# MOD-EEG-SMT.net
KiCad netlist of a schematic drawn in EAGLE
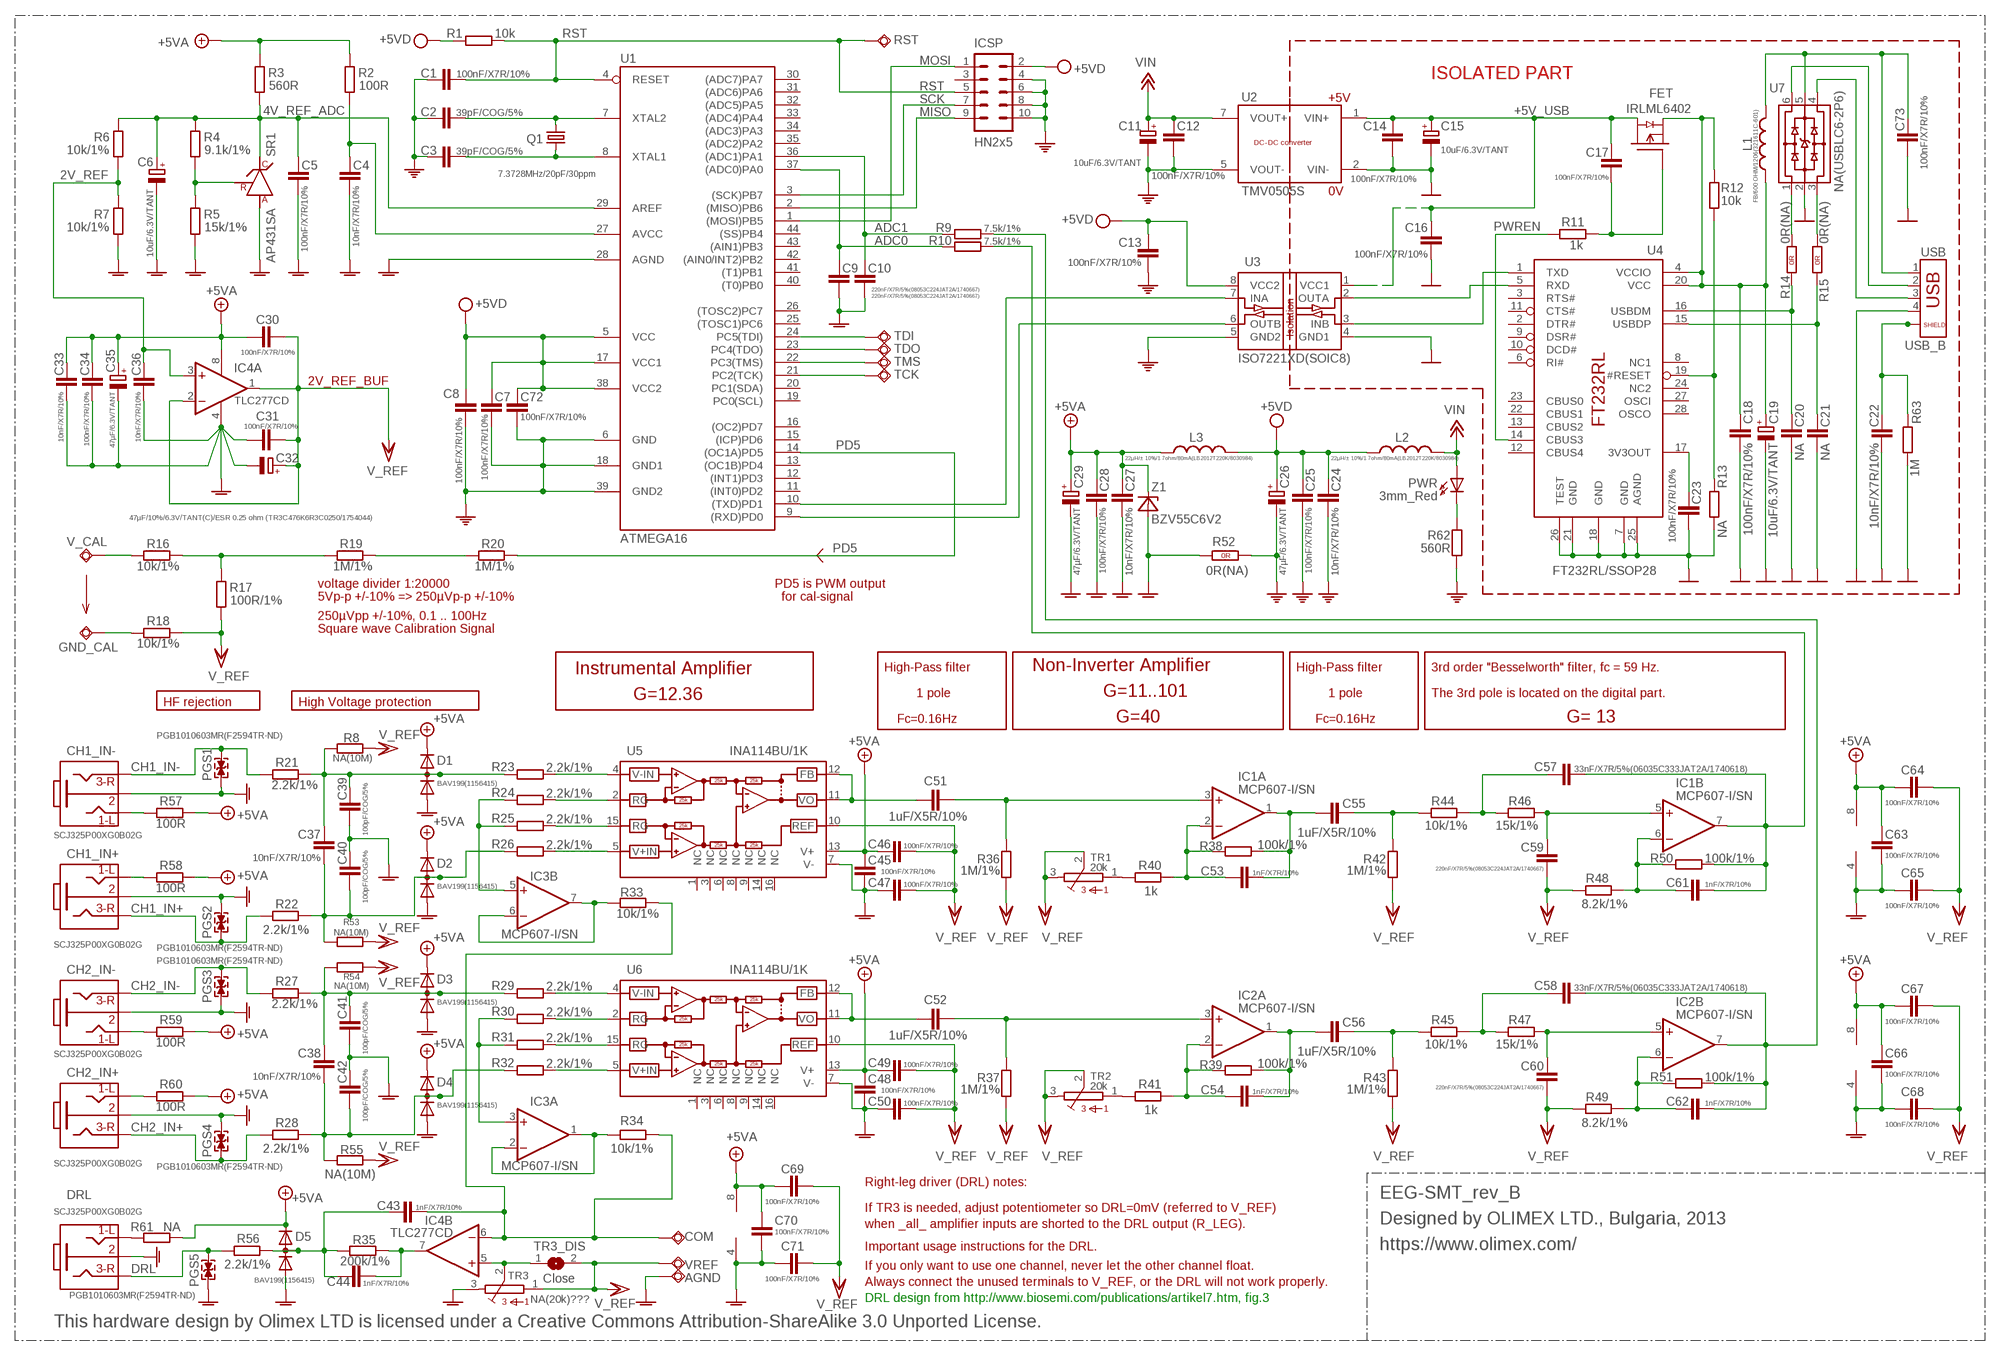
[diagram p0: schematic, sheet 1]

(export (version "E")
  (design (tool "Eeschema 10.0.6"))
  (components
    (comp (ref "AGND")
      (value "TESTPAD3")
      (footprint "eagle-import:TEST_PAD40_70_SQUARE")
      (libsource (lib "eagle-import") (part "TESTPAD3"))
    )
    (comp (ref "C1")
      (value "100nF/X7R/10%")
      (footprint "eagle-import:C0603_DWS")
      (libsource (lib "eagle-import") (part "C-EUC0603_DWS"))
    )
    (comp (ref "C2")
      (value "39pF/COG/5%")
      (footprint "eagle-import:C0603_DWS")
      (libsource (lib "eagle-import") (part "C-EUC0603_DWS"))
    )
    (comp (ref "C3")
      (value "39pF/COG/5%")
      (footprint "eagle-import:C0603_DWS")
      (libsource (lib "eagle-import") (part "C-EUC0603_DWS"))
    )
    (comp (ref "C4")
      (value "10nF/X7R/10%")
      (footprint "eagle-import:C0603_DWS")
      (libsource (lib "eagle-import") (part "C-EUC0603_DWS"))
    )
    (comp (ref "C5")
      (value "100nF/X7R/10%")
      (footprint "eagle-import:C0603_DWS")
      (libsource (lib "eagle-import") (part "C-EUC0603_DWS"))
    )
    (comp (ref "C6")
      (value "10uF/6.3V/TANT")
      (footprint "eagle-import:CT3216")
      (libsource (lib "eagle-import") (part "CPOL-EUCT3216"))
    )
    (comp (ref "C7")
      (value "100nF/X7R/10%")
      (footprint "eagle-import:C0603_DWS")
      (libsource (lib "eagle-import") (part "C-EUC0603_DWS"))
    )
    (comp (ref "C8")
      (value "100nF/X7R/10%")
      (footprint "eagle-import:C0603_DWS")
      (libsource (lib "eagle-import") (part "C-EUC0603_DWS"))
    )
    (comp (ref "C9")
      (value "220nF/X7R/5%(08053C224JAT2A/1740667)")
      (footprint "eagle-import:C0805_5MIL_DWS")
      (libsource (lib "eagle-import") (part "C-EUC0805_5MIL_DWS"))
    )
    (comp (ref "C10")
      (value "220nF/X7R/5%(08053C224JAT2A/1740667)")
      (footprint "eagle-import:C0805_5MIL_DWS")
      (libsource (lib "eagle-import") (part "C-EUC0805_5MIL_DWS"))
    )
    (comp (ref "C11")
      (value "10uF/6.3V/TANT")
      (footprint "eagle-import:CT3216")
      (libsource (lib "eagle-import") (part "CPOL-EUCT3216"))
    )
    (comp (ref "C12")
      (value "100nF/X7R/10%")
      (footprint "eagle-import:C0603_DWS")
      (libsource (lib "eagle-import") (part "C-EUC0603_DWS"))
    )
    (comp (ref "C13")
      (value "100nF/X7R/10%")
      (footprint "eagle-import:C0603_DWS")
      (libsource (lib "eagle-import") (part "C-EUC0603_DWS"))
    )
    (comp (ref "C14")
      (value "100nF/X7R/10%")
      (footprint "eagle-import:C0603_DWS")
      (libsource (lib "eagle-import") (part "C-EUC0603_DWS"))
    )
    (comp (ref "C15")
      (value "10uF/6.3V/TANT")
      (footprint "eagle-import:CT3216")
      (libsource (lib "eagle-import") (part "CPOL-EUCT3216"))
    )
    (comp (ref "C16")
      (value "100nF/X7R/10%")
      (footprint "eagle-import:C0603_DWS")
      (libsource (lib "eagle-import") (part "C-EUC0603_DWS"))
    )
    (comp (ref "C17")
      (value "100nF/X7R/10%")
      (footprint "eagle-import:C0603_DWS")
      (libsource (lib "eagle-import") (part "C-EUC0603_DWS"))
    )
    (comp (ref "C18")
      (value "100nF/X7R/10%")
      (footprint "eagle-import:C0603_DWS")
      (libsource (lib "eagle-import") (part "C-EUC0603_DWS"))
    )
    (comp (ref "C19")
      (value "10uF/6.3V/TANT")
      (footprint "eagle-import:CT3216")
      (libsource (lib "eagle-import") (part "CPOL-EUCT3216"))
    )
    (comp (ref "C20")
      (value "NA")
      (footprint "eagle-import:C0603_DWS_NA")
      (libsource (lib "eagle-import") (part "C-EUC0603_DWS_NA"))
    )
    (comp (ref "C21")
      (value "NA")
      (footprint "eagle-import:C0603_DWS_NA")
      (libsource (lib "eagle-import") (part "C-EUC0603_DWS_NA"))
    )
    (comp (ref "C22")
      (value "10nF/X7R/10%")
      (footprint "eagle-import:C0603_DWS")
      (libsource (lib "eagle-import") (part "C-EUC0603_DWS"))
    )
    (comp (ref "C23")
      (value "100nF/X7R/10%")
      (footprint "eagle-import:C0603_DWS")
      (libsource (lib "eagle-import") (part "C-EUC0603_DWS"))
    )
    (comp (ref "C24")
      (value "10nF/X7R/10%")
      (footprint "eagle-import:C0603_DWS")
      (libsource (lib "eagle-import") (part "C-EUC0603_DWS"))
    )
    (comp (ref "C25")
      (value "100nF/X7R/10%")
      (footprint "eagle-import:C0603_DWS")
      (libsource (lib "eagle-import") (part "C-EUC0603_DWS"))
    )
    (comp (ref "C26")
      (value "47µF/6.3V/TANT")
      (footprint "eagle-import:CT3528")
      (libsource (lib "eagle-import") (part "CPOL-EUCT3528"))
    )
    (comp (ref "C27")
      (value "10nF/X7R/10%")
      (footprint "eagle-import:C0603_DWS")
      (libsource (lib "eagle-import") (part "C-EUC0603_DWS"))
    )
    (comp (ref "C28")
      (value "100nF/X7R/10%")
      (footprint "eagle-import:C0603_DWS")
      (libsource (lib "eagle-import") (part "C-EUC0603_DWS"))
    )
    (comp (ref "C29")
      (value "47µF/6.3V/TANT")
      (footprint "eagle-import:CT3528")
      (libsource (lib "eagle-import") (part "CPOL-EUCT3528"))
    )
    (comp (ref "C30")
      (value "100nF/X7R/10%")
      (footprint "eagle-import:C0603_DWS")
      (libsource (lib "eagle-import") (part "C-EUC0603_DWS"))
    )
    (comp (ref "C31")
      (value "100nF/X7R/10%")
      (footprint "eagle-import:C0603_DWS")
      (libsource (lib "eagle-import") (part "C-EUC0603_DWS"))
    )
    (comp (ref "C32")
      (value "47µF/10%/6.3V/TANT(C)/ESR 0.25 ohm (TR3C476K6R3C0250/1754044)")
      (footprint "eagle-import:CT6032")
      (libsource (lib "eagle-import") (part "CPOL-EUCT6032"))
    )
    (comp (ref "C33")
      (value "10nF/X7R/10%")
      (footprint "eagle-import:C0603_DWS")
      (libsource (lib "eagle-import") (part "C-EUC0603_DWS"))
    )
    (comp (ref "C34")
      (value "100nF/X7R/10%")
      (footprint "eagle-import:C0603_DWS")
      (libsource (lib "eagle-import") (part "C-EUC0603_DWS"))
    )
    (comp (ref "C35")
      (value "47µF/6.3V/TANT")
      (footprint "eagle-import:CT3528")
      (libsource (lib "eagle-import") (part "CPOL-EUCT3528"))
    )
    (comp (ref "C36")
      (value "10nF/X7R/10%")
      (footprint "eagle-import:C0603_DWS")
      (libsource (lib "eagle-import") (part "C-EUC0603_DWS"))
    )
    (comp (ref "C37")
      (value "10nF/X7R/10%")
      (footprint "eagle-import:C0603_DWS")
      (libsource (lib "eagle-import") (part "C-EUC0603_DWS"))
    )
    (comp (ref "C38")
      (value "10nF/X7R/10%")
      (footprint "eagle-import:C0603_DWS")
      (libsource (lib "eagle-import") (part "C-EUC0603_DWS"))
    )
    (comp (ref "C39")
      (value "100pF/COG/5%")
      (footprint "eagle-import:C0603_DWS")
      (libsource (lib "eagle-import") (part "C-EUC0603_DWS"))
    )
    (comp (ref "C40")
      (value "100pF/COG/5%")
      (footprint "eagle-import:C0603_DWS")
      (libsource (lib "eagle-import") (part "C-EUC0603_DWS"))
    )
    (comp (ref "C41")
      (value "100pF/COG/5%")
      (footprint "eagle-import:C0603_DWS")
      (libsource (lib "eagle-import") (part "C-EUC0603_DWS"))
    )
    (comp (ref "C42")
      (value "100pF/COG/5%")
      (footprint "eagle-import:C0603_DWS")
      (libsource (lib "eagle-import") (part "C-EUC0603_DWS"))
    )
    (comp (ref "C43")
      (value "1nF/X7R/10%")
      (footprint "eagle-import:C0603_DWS")
      (libsource (lib "eagle-import") (part "C-EUC0603_DWS"))
    )
    (comp (ref "C44")
      (value "1nF/X7R/10%")
      (footprint "eagle-import:C0603_DWS")
      (libsource (lib "eagle-import") (part "C-EUC0603_DWS"))
    )
    (comp (ref "C45")
      (value "100nF/X7R/10%")
      (footprint "eagle-import:C0603_DWS")
      (libsource (lib "eagle-import") (part "C-EUC0603_DWS"))
    )
    (comp (ref "C46")
      (value "100nF/X7R/10%")
      (footprint "eagle-import:C0603_DWS")
      (libsource (lib "eagle-import") (part "C-EUC0603_DWS"))
    )
    (comp (ref "C47")
      (value "100nF/X7R/10%")
      (footprint "eagle-import:C0603_DWS")
      (libsource (lib "eagle-import") (part "C-EUC0603_DWS"))
    )
    (comp (ref "C48")
      (value "100nF/X7R/10%")
      (footprint "eagle-import:C0603_DWS")
      (libsource (lib "eagle-import") (part "C-EUC0603_DWS"))
    )
    (comp (ref "C49")
      (value "100nF/X7R/10%")
      (footprint "eagle-import:C0603_DWS")
      (libsource (lib "eagle-import") (part "C-EUC0603_DWS"))
    )
    (comp (ref "C50")
      (value "100nF/X7R/10%")
      (footprint "eagle-import:C0603_DWS")
      (libsource (lib "eagle-import") (part "C-EUC0603_DWS"))
    )
    (comp (ref "C51")
      (value "1uF/X5R/10%")
      (footprint "eagle-import:C0603_DWS")
      (libsource (lib "eagle-import") (part "C-EUC0603_DWS"))
    )
    (comp (ref "C52")
      (value "1uF/X5R/10%")
      (footprint "eagle-import:C0603_DWS")
      (libsource (lib "eagle-import") (part "C-EUC0603_DWS"))
    )
    (comp (ref "C53")
      (value "1nF/X7R/10%")
      (footprint "eagle-import:C0603_DWS")
      (libsource (lib "eagle-import") (part "C-EUC0603_DWS"))
    )
    (comp (ref "C54")
      (value "1nF/X7R/10%")
      (footprint "eagle-import:C0603_DWS")
      (libsource (lib "eagle-import") (part "C-EUC0603_DWS"))
    )
    (comp (ref "C55")
      (value "1uF/X5R/10%")
      (footprint "eagle-import:C0603_DWS")
      (libsource (lib "eagle-import") (part "C-EUC0603_DWS"))
    )
    (comp (ref "C56")
      (value "1uF/X5R/10%")
      (footprint "eagle-import:C0603_DWS")
      (libsource (lib "eagle-import") (part "C-EUC0603_DWS"))
    )
    (comp (ref "C57")
      (value "33nF/X7R/5%(06035C333JAT2A/1740618)")
      (footprint "eagle-import:C0603_DWS")
      (libsource (lib "eagle-import") (part "C-EUC0603_DWS"))
    )
    (comp (ref "C58")
      (value "33nF/X7R/5%(06035C333JAT2A/1740618)")
      (footprint "eagle-import:C0603_DWS")
      (libsource (lib "eagle-import") (part "C-EUC0603_DWS"))
    )
    (comp (ref "C59")
      (value "220nF/X7R/5%(08053C224JAT2A/1740667)")
      (footprint "eagle-import:C0805_5MIL_DWS")
      (libsource (lib "eagle-import") (part "C-EUC0805_5MIL_DWS"))
    )
    (comp (ref "C60")
      (value "220nF/X7R/5%(08053C224JAT2A/1740667)")
      (footprint "eagle-import:C0805_5MIL_DWS")
      (libsource (lib "eagle-import") (part "C-EUC0805_5MIL_DWS"))
    )
    (comp (ref "C61")
      (value "1nF/X7R/10%")
      (footprint "eagle-import:C0603_DWS")
      (libsource (lib "eagle-import") (part "C-EUC0603_DWS"))
    )
    (comp (ref "C62")
      (value "1nF/X7R/10%")
      (footprint "eagle-import:C0603_DWS")
      (libsource (lib "eagle-import") (part "C-EUC0603_DWS"))
    )
    (comp (ref "C63")
      (value "100nF/X7R/10%")
      (footprint "eagle-import:C0603_DWS")
      (libsource (lib "eagle-import") (part "C-EUC0603_DWS"))
    )
    (comp (ref "C64")
      (value "100nF/X7R/10%")
      (footprint "eagle-import:C0603_DWS")
      (libsource (lib "eagle-import") (part "C-EUC0603_DWS"))
    )
    (comp (ref "C65")
      (value "100nF/X7R/10%")
      (footprint "eagle-import:C0603_DWS")
      (libsource (lib "eagle-import") (part "C-EUC0603_DWS"))
    )
    (comp (ref "C66")
      (value "100nF/X7R/10%")
      (footprint "eagle-import:C0603_DWS")
      (libsource (lib "eagle-import") (part "C-EUC0603_DWS"))
    )
    (comp (ref "C67")
      (value "100nF/X7R/10%")
      (footprint "eagle-import:C0603_DWS")
      (libsource (lib "eagle-import") (part "C-EUC0603_DWS"))
    )
    (comp (ref "C68")
      (value "100nF/X7R/10%")
      (footprint "eagle-import:C0603_DWS")
      (libsource (lib "eagle-import") (part "C-EUC0603_DWS"))
    )
    (comp (ref "C69")
      (value "100nF/X7R/10%")
      (footprint "eagle-import:C0603_DWS")
      (libsource (lib "eagle-import") (part "C-EUC0603_DWS"))
    )
    (comp (ref "C70")
      (value "100nF/X7R/10%")
      (footprint "eagle-import:C0603_DWS")
      (libsource (lib "eagle-import") (part "C-EUC0603_DWS"))
    )
    (comp (ref "C71")
      (value "100nF/X7R/10%")
      (footprint "eagle-import:C0603_DWS")
      (libsource (lib "eagle-import") (part "C-EUC0603_DWS"))
    )
    (comp (ref "C72")
      (value "100nF/X7R/10%")
      (footprint "eagle-import:C0603_DWS")
      (libsource (lib "eagle-import") (part "C-EUC0603_DWS"))
    )
    (comp (ref "C73")
      (value "100nF/X7R/10%")
      (footprint "eagle-import:C0603_DWS")
      (libsource (lib "eagle-import") (part "C-EUC0603_DWS"))
    )
    (comp (ref "CH1_IN+")
      (value "SCJ325P00XG0B02G")
      (footprint "eagle-import:PHONE_JACK-SMD")
      (libsource (lib "eagle-import") (part "JACK-3PINPHONE_JACK-SMD"))
    )
    (comp (ref "CH1_IN-")
      (value "SCJ325P00XG0B02G")
      (footprint "eagle-import:PHONE_JACK-SMD")
      (libsource (lib "eagle-import") (part "JACK-3PINPHONE_JACK-SMD"))
    )
    (comp (ref "CH2_IN+")
      (value "SCJ325P00XG0B02G")
      (footprint "eagle-import:PHONE_JACK-SMD")
      (libsource (lib "eagle-import") (part "JACK-3PINPHONE_JACK-SMD"))
    )
    (comp (ref "CH2_IN-")
      (value "SCJ325P00XG0B02G")
      (footprint "eagle-import:PHONE_JACK-SMD")
      (libsource (lib "eagle-import") (part "JACK-3PINPHONE_JACK-SMD"))
    )
    (comp (ref "COM")
      (value "TESTPAD3")
      (footprint "eagle-import:TEST_PAD40_70_SQUARE")
      (libsource (lib "eagle-import") (part "TESTPAD3"))
    )
    (comp (ref "D1")
      (value "BAV199(1156415)")
      (footprint "eagle-import:SOT23C(BAT54S)")
      (libsource (lib "eagle-import") (part "DIODE_AC-AC_"))
    )
    (comp (ref "D2")
      (value "BAV199(1156415)")
      (footprint "eagle-import:SOT23C(BAT54S)")
      (libsource (lib "eagle-import") (part "DIODE_AC-AC_"))
    )
    (comp (ref "D3")
      (value "BAV199(1156415)")
      (footprint "eagle-import:SOT23C(BAT54S)")
      (libsource (lib "eagle-import") (part "DIODE_AC-AC_"))
    )
    (comp (ref "D4")
      (value "BAV199(1156415)")
      (footprint "eagle-import:SOT23C(BAT54S)")
      (libsource (lib "eagle-import") (part "DIODE_AC-AC_"))
    )
    (comp (ref "D5")
      (value "BAV199(1156415)")
      (footprint "eagle-import:SOT23C(BAT54S)")
      (libsource (lib "eagle-import") (part "DIODE_AC-AC_"))
    )
    (comp (ref "DRL")
      (value "SCJ325P00XG0B02G")
      (footprint "eagle-import:PHONE_JACK-SMD")
      (libsource (lib "eagle-import") (part "JACK-3PINPHONE_JACK-SMD"))
    )
    (comp (ref "FET")
      (value "IRLML6402")
      (footprint "eagle-import:SOT23")
      (libsource (lib "eagle-import") (part "IRLML6402"))
    )
    (comp (ref "GND_CAL")
      (value "TESTPAD3")
      (footprint "eagle-import:TEST_PAD40_70_SQUARE")
      (libsource (lib "eagle-import") (part "TESTPAD3"))
    )
    (comp (ref "IC1")
      (value "MCP607-I/SN")
      (footprint "eagle-import:SO08")
      (libsource (lib "eagle-import") (part "LM358D"))
    )
    (comp (ref "IC2")
      (value "MCP607-I/SN")
      (footprint "eagle-import:SO08")
      (libsource (lib "eagle-import") (part "LM358D"))
    )
    (comp (ref "IC3")
      (value "MCP607-I/SN")
      (footprint "eagle-import:SO08")
      (libsource (lib "eagle-import") (part "LM358D"))
    )
    (comp (ref "IC4")
      (value "TLC277CD")
      (footprint "eagle-import:SO08")
      (libsource (lib "eagle-import") (part "LM358D"))
    )
    (comp (ref "ICSP")
      (value "HN2x5")
      (footprint "eagle-import:ML10_NEW")
      (libsource (lib "eagle-import") (part "ML10ML10_NEW"))
    )
    (comp (ref "L1")
      (value "FB/600 OHM/1206(321611C-601)")
      (footprint "eagle-import:L1206_5MIL")
      (libsource (lib "eagle-import") (part "L-US1206_5MIL"))
    )
    (comp (ref "L2")
      (value "22µH/± 10%/1.7ohm/80mA(LB2012T220K/8030984)")
      (footprint "eagle-import:L0805_5MIL_DWS")
      (libsource (lib "eagle-import") (part "L-USL0805_5MIL_DWS"))
    )
    (comp (ref "L3")
      (value "22µH/± 10%/1.7ohm/80mA(LB2012T220K/8030984)")
      (footprint "eagle-import:L0805_5MIL_DWS")
      (libsource (lib "eagle-import") (part "L-USL0805_5MIL_DWS"))
    )
    (comp (ref "PGS1")
      (value "PGB1010603MR(F2594TR-ND)")
      (footprint "eagle-import:0603")
      (libsource (lib "eagle-import") (part "PGB1010603MR(F2594TR-ND)"))
    )
    (comp (ref "PGS2")
      (value "PGB1010603MR(F2594TR-ND)")
      (footprint "eagle-import:0603")
      (libsource (lib "eagle-import") (part "PGB1010603MR(F2594TR-ND)"))
    )
    (comp (ref "PGS3")
      (value "PGB1010603MR(F2594TR-ND)")
      (footprint "eagle-import:0603")
      (libsource (lib "eagle-import") (part "PGB1010603MR(F2594TR-ND)"))
    )
    (comp (ref "PGS4")
      (value "PGB1010603MR(F2594TR-ND)")
      (footprint "eagle-import:0603")
      (libsource (lib "eagle-import") (part "PGB1010603MR(F2594TR-ND)"))
    )
    (comp (ref "PGS5")
      (value "PGB1010603MR(F2594TR-ND)")
      (footprint "eagle-import:0603")
      (libsource (lib "eagle-import") (part "PGB1010603MR(F2594TR-ND)"))
    )
    (comp (ref "PWR")
      (value "3mm_Red")
      (footprint "eagle-import:LED-3.0MM")
      (libsource (lib "eagle-import") (part "LED3.0MM"))
    )
    (comp (ref "Q1")
      (value "7.3728MHz/20pF/30ppm")
      (footprint "eagle-import:HC49_SMD2_THIN")
      (libsource (lib "eagle-import") (part "HC49/S1"))
    )
    (comp (ref "R1")
      (value "10k")
      (footprint "eagle-import:R0603_5MIL_DWS")
      (libsource (lib "eagle-import") (part "R-EU_R0603_5MIL_DWS"))
    )
    (comp (ref "R2")
      (value "100R")
      (footprint "eagle-import:R0603_5MIL_DWS")
      (libsource (lib "eagle-import") (part "R-EU_R0603_5MIL_DWS"))
    )
    (comp (ref "R3")
      (value "560R")
      (footprint "eagle-import:R0603_5MIL_DWS")
      (libsource (lib "eagle-import") (part "R-EU_R0603_5MIL_DWS"))
    )
    (comp (ref "R4")
      (value "9.1k/1%")
      (footprint "eagle-import:R0603_5MIL_DWS")
      (libsource (lib "eagle-import") (part "R-EU_R0603_5MIL_DWS"))
    )
    (comp (ref "R5")
      (value "15k/1%")
      (footprint "eagle-import:R0603_5MIL_DWS")
      (libsource (lib "eagle-import") (part "R-EU_R0603_5MIL_DWS"))
    )
    (comp (ref "R6")
      (value "10k/1%")
      (footprint "eagle-import:R0603_5MIL_DWS")
      (libsource (lib "eagle-import") (part "R-EU_R0603_5MIL_DWS"))
    )
    (comp (ref "R7")
      (value "10k/1%")
      (footprint "eagle-import:R0603_5MIL_DWS")
      (libsource (lib "eagle-import") (part "R-EU_R0603_5MIL_DWS"))
    )
    (comp (ref "R8")
      (value "NA(10M)")
      (footprint "eagle-import:R0603_5MIL_DWS")
      (libsource (lib "eagle-import") (part "R-EU_R0603_5MIL_DWS"))
    )
    (comp (ref "R9")
      (value "7.5k/1%")
      (footprint "eagle-import:R0603_5MIL_DWS")
      (libsource (lib "eagle-import") (part "R-EU_R0603_5MIL_DWS"))
    )
    (comp (ref "R10")
      (value "7.5k/1%")
      (footprint "eagle-import:R0603_5MIL_DWS")
      (libsource (lib "eagle-import") (part "R-EU_R0603_5MIL_DWS"))
    )
    (comp (ref "R11")
      (value "1k")
      (footprint "eagle-import:R0603_5MIL_DWS")
      (libsource (lib "eagle-import") (part "R-EU_R0603_5MIL_DWS"))
    )
    (comp (ref "R12")
      (value "10k")
      (footprint "eagle-import:R0603_5MIL_DWS")
      (libsource (lib "eagle-import") (part "R-EU_R0603_5MIL_DWS"))
    )
    (comp (ref "R13")
      (value "NA")
      (footprint "eagle-import:R0603_5MIL_DWS_NA")
      (libsource (lib "eagle-import") (part "R-EU_R0603_5MIL_DWS_NA"))
    )
    (comp (ref "R14")
      (value "0R(NA)")
      (footprint "eagle-import:0603_0R")
      (libsource (lib "eagle-import") (part "R_0R0R(NA)"))
    )
    (comp (ref "R15")
      (value "0R(NA)")
      (footprint "eagle-import:0603_0R")
      (libsource (lib "eagle-import") (part "R_0R0R(NA)"))
    )
    (comp (ref "R16")
      (value "10k/1%")
      (footprint "eagle-import:R0603_5MIL_DWS")
      (libsource (lib "eagle-import") (part "R-EU_R0603_5MIL_DWS"))
    )
    (comp (ref "R17")
      (value "100R/1%")
      (footprint "eagle-import:R0603_5MIL_DWS")
      (libsource (lib "eagle-import") (part "R-EU_R0603_5MIL_DWS"))
    )
    (comp (ref "R18")
      (value "10k/1%")
      (footprint "eagle-import:R0603_5MIL_DWS")
      (libsource (lib "eagle-import") (part "R-EU_R0603_5MIL_DWS"))
    )
    (comp (ref "R19")
      (value "1M/1%")
      (footprint "eagle-import:R0603_5MIL_DWS")
      (libsource (lib "eagle-import") (part "R-EU_R0603_5MIL_DWS"))
    )
    (comp (ref "R20")
      (value "1M/1%")
      (footprint "eagle-import:R0603_5MIL_DWS")
      (libsource (lib "eagle-import") (part "R-EU_R0603_5MIL_DWS"))
    )
    (comp (ref "R21")
      (value "2.2k/1%")
      (footprint "eagle-import:R0603_5MIL_DWS")
      (libsource (lib "eagle-import") (part "R-EU_R0603_5MIL_DWS"))
    )
    (comp (ref "R22")
      (value "2.2k/1%")
      (footprint "eagle-import:R0603_5MIL_DWS")
      (libsource (lib "eagle-import") (part "R-EU_R0603_5MIL_DWS"))
    )
    (comp (ref "R23")
      (value "2.2k/1%")
      (footprint "eagle-import:R0603_5MIL_DWS")
      (libsource (lib "eagle-import") (part "R-EU_R0603_5MIL_DWS"))
    )
    (comp (ref "R24")
      (value "2.2k/1%")
      (footprint "eagle-import:R0603_5MIL_DWS")
      (libsource (lib "eagle-import") (part "R-EU_R0603_5MIL_DWS"))
    )
    (comp (ref "R25")
      (value "2.2k/1%")
      (footprint "eagle-import:R0603_5MIL_DWS")
      (libsource (lib "eagle-import") (part "R-EU_R0603_5MIL_DWS"))
    )
    (comp (ref "R26")
      (value "2.2k/1%")
      (footprint "eagle-import:R0603_5MIL_DWS")
      (libsource (lib "eagle-import") (part "R-EU_R0603_5MIL_DWS"))
    )
    (comp (ref "R27")
      (value "2.2k/1%")
      (footprint "eagle-import:R0603_5MIL_DWS")
      (libsource (lib "eagle-import") (part "R-EU_R0603_5MIL_DWS"))
    )
    (comp (ref "R28")
      (value "2.2k/1%")
      (footprint "eagle-import:R0603_5MIL_DWS")
      (libsource (lib "eagle-import") (part "R-EU_R0603_5MIL_DWS"))
    )
    (comp (ref "R29")
      (value "2.2k/1%")
      (footprint "eagle-import:R0603_5MIL_DWS")
      (libsource (lib "eagle-import") (part "R-EU_R0603_5MIL_DWS"))
    )
    (comp (ref "R30")
      (value "2.2k/1%")
      (footprint "eagle-import:R0603_5MIL_DWS")
      (libsource (lib "eagle-import") (part "R-EU_R0603_5MIL_DWS"))
    )
    (comp (ref "R31")
      (value "2.2k/1%")
      (footprint "eagle-import:R0603_5MIL_DWS")
      (libsource (lib "eagle-import") (part "R-EU_R0603_5MIL_DWS"))
    )
    (comp (ref "R32")
      (value "2.2k/1%")
      (footprint "eagle-import:R0603_5MIL_DWS")
      (libsource (lib "eagle-import") (part "R-EU_R0603_5MIL_DWS"))
    )
    (comp (ref "R33")
      (value "10k/1%")
      (footprint "eagle-import:R0603_5MIL_DWS")
      (libsource (lib "eagle-import") (part "R-EU_R0603_5MIL_DWS"))
    )
    (comp (ref "R34")
      (value "10k/1%")
      (footprint "eagle-import:R0603_5MIL_DWS")
      (libsource (lib "eagle-import") (part "R-EU_R0603_5MIL_DWS"))
    )
    (comp (ref "R35")
      (value "200k/1%")
      (footprint "eagle-import:R0603_5MIL_DWS")
      (libsource (lib "eagle-import") (part "R-EU_R0603_5MIL_DWS"))
    )
    (comp (ref "R36")
      (value "1M/1%")
      (footprint "eagle-import:R0603_5MIL_DWS")
      (libsource (lib "eagle-import") (part "R-EU_R0603_5MIL_DWS"))
    )
    (comp (ref "R37")
      (value "1M/1%")
      (footprint "eagle-import:R0603_5MIL_DWS")
      (libsource (lib "eagle-import") (part "R-EU_R0603_5MIL_DWS"))
    )
    (comp (ref "R38")
      (value "100k/1%")
      (footprint "eagle-import:R0603_5MIL_DWS")
      (libsource (lib "eagle-import") (part "R-EU_R0603_5MIL_DWS"))
    )
    (comp (ref "R39")
      (value "100k/1%")
      (footprint "eagle-import:R0603_5MIL_DWS")
      (libsource (lib "eagle-import") (part "R-EU_R0603_5MIL_DWS"))
    )
    (comp (ref "R40")
      (value "1k")
      (footprint "eagle-import:R0603_5MIL_DWS")
      (libsource (lib "eagle-import") (part "R-EU_R0603_5MIL_DWS"))
    )
    (comp (ref "R41")
      (value "1k")
      (footprint "eagle-import:R0603_5MIL_DWS")
      (libsource (lib "eagle-import") (part "R-EU_R0603_5MIL_DWS"))
    )
    (comp (ref "R42")
      (value "1M/1%")
      (footprint "eagle-import:R0603_5MIL_DWS")
      (libsource (lib "eagle-import") (part "R-EU_R0603_5MIL_DWS"))
    )
    (comp (ref "R43")
      (value "1M/1%")
      (footprint "eagle-import:R0603_5MIL_DWS")
      (libsource (lib "eagle-import") (part "R-EU_R0603_5MIL_DWS"))
    )
    (comp (ref "R44")
      (value "10k/1%")
      (footprint "eagle-import:R0603_5MIL_DWS")
      (libsource (lib "eagle-import") (part "R-EU_R0603_5MIL_DWS"))
    )
    (comp (ref "R45")
      (value "10k/1%")
      (footprint "eagle-import:R0603_5MIL_DWS")
      (libsource (lib "eagle-import") (part "R-EU_R0603_5MIL_DWS"))
    )
    (comp (ref "R46")
      (value "15k/1%")
      (footprint "eagle-import:R0603_5MIL_DWS")
      (libsource (lib "eagle-import") (part "R-EU_R0603_5MIL_DWS"))
    )
    (comp (ref "R47")
      (value "15k/1%")
      (footprint "eagle-import:R0603_5MIL_DWS")
      (libsource (lib "eagle-import") (part "R-EU_R0603_5MIL_DWS"))
    )
    (comp (ref "R48")
      (value "8.2k/1%")
      (footprint "eagle-import:R0603_5MIL_DWS")
      (libsource (lib "eagle-import") (part "R-EU_R0603_5MIL_DWS"))
    )
    (comp (ref "R49")
      (value "8.2k/1%")
      (footprint "eagle-import:R0603_5MIL_DWS")
      (libsource (lib "eagle-import") (part "R-EU_R0603_5MIL_DWS"))
    )
    (comp (ref "R50")
      (value "100k/1%")
      (footprint "eagle-import:R0603_5MIL_DWS")
      (libsource (lib "eagle-import") (part "R-EU_R0603_5MIL_DWS"))
    )
    (comp (ref "R51")
      (value "100k/1%")
      (footprint "eagle-import:R0603_5MIL_DWS")
      (libsource (lib "eagle-import") (part "R-EU_R0603_5MIL_DWS"))
    )
    (comp (ref "R52")
      (value "0R(NA)")
      (footprint "eagle-import:0603_0R")
      (libsource (lib "eagle-import") (part "R_0R0R(NA)"))
    )
    (comp (ref "R53")
      (value "NA(10M)")
      (footprint "eagle-import:R0603_5MIL_DWS")
      (libsource (lib "eagle-import") (part "R-EU_R0603_5MIL_DWS"))
    )
    (comp (ref "R54")
      (value "NA(10M)")
      (footprint "eagle-import:R0603_5MIL_DWS")
      (libsource (lib "eagle-import") (part "R-EU_R0603_5MIL_DWS"))
    )
    (comp (ref "R55")
      (value "NA(10M)")
      (footprint "eagle-import:R0603_5MIL_DWS")
      (libsource (lib "eagle-import") (part "R-EU_R0603_5MIL_DWS"))
    )
    (comp (ref "R56")
      (value "2.2k/1%")
      (footprint "eagle-import:R0603_5MIL_DWS")
      (libsource (lib "eagle-import") (part "R-EU_R0603_5MIL_DWS"))
    )
    (comp (ref "R57")
      (value "100R")
      (footprint "eagle-import:R0603_5MIL_DWS")
      (libsource (lib "eagle-import") (part "R-EU_R0603_5MIL_DWS"))
    )
    (comp (ref "R58")
      (value "100R")
      (footprint "eagle-import:R0603_5MIL_DWS")
      (libsource (lib "eagle-import") (part "R-EU_R0603_5MIL_DWS"))
    )
    (comp (ref "R59")
      (value "100R")
      (footprint "eagle-import:R0603_5MIL_DWS")
      (libsource (lib "eagle-import") (part "R-EU_R0603_5MIL_DWS"))
    )
    (comp (ref "R60")
      (value "100R")
      (footprint "eagle-import:R0603_5MIL_DWS")
      (libsource (lib "eagle-import") (part "R-EU_R0603_5MIL_DWS"))
    )
    (comp (ref "R61")
      (value "NA")
      (footprint "eagle-import:R0603_5MIL_DWS_NA")
      (libsource (lib "eagle-import") (part "R-EU_R0603_5MIL_DWS_NA"))
    )
    (comp (ref "R62")
      (value "560R")
      (footprint "eagle-import:R0603_5MIL_DWS")
      (libsource (lib "eagle-import") (part "R-EU_R0603_5MIL_DWS"))
    )
    (comp (ref "R63")
      (value "1M")
      (footprint "eagle-import:R0603_5MIL_DWS")
      (libsource (lib "eagle-import") (part "R-EU_R0603_5MIL_DWS"))
    )
    (comp (ref "RST")
      (value "TESTPAD80/30")
      (footprint "eagle-import:SMD80_30")
      (libsource (lib "eagle-import") (part "TESTPAD80/30"))
    )
    (comp (ref "SR1")
      (value "AP431SA")
      (footprint "eagle-import:SOT-23")
      (libsource (lib "eagle-import") (part "TL431'''"))
    )
    (comp (ref "TCK")
      (value "TESTPAD80/30")
      (footprint "eagle-import:SMD80_30")
      (libsource (lib "eagle-import") (part "TESTPAD80/30"))
    )
    (comp (ref "TDI")
      (value "TESTPAD80/30")
      (footprint "eagle-import:SMD80_30")
      (libsource (lib "eagle-import") (part "TESTPAD80/30"))
    )
    (comp (ref "TDO")
      (value "TESTPAD80/30")
      (footprint "eagle-import:SMD80_30")
      (libsource (lib "eagle-import") (part "TESTPAD80/30"))
    )
    (comp (ref "TMS")
      (value "TESTPAD80/30")
      (footprint "eagle-import:SMD80_30")
      (libsource (lib "eagle-import") (part "TESTPAD80/30"))
    )
    (comp (ref "TR1")
      (value "20k")
      (footprint "eagle-import:S64Y")
      (libsource (lib "eagle-import") (part "S64Y"))
    )
    (comp (ref "TR2")
      (value "20k")
      (footprint "eagle-import:S64Y")
      (libsource (lib "eagle-import") (part "S64Y"))
    )
    (comp (ref "TR3")
      (value "NA(20k)???")
      (footprint "eagle-import:S64Y")
      (libsource (lib "eagle-import") (part "S64Y"))
    )
    (comp (ref "TR3_DIS")
      (value "Close")
      (footprint "eagle-import:SJ_1_SMALLER")
      (libsource (lib "eagle-import") (part "SJSJ_SMALLER"))
    )
    (comp (ref "U1")
      (value "ATMEGA16")
      (footprint "eagle-import:44TQFP")
      (libsource (lib "eagle-import") (part "ATMEGA16"))
    )
    (comp (ref "U2")
      (value "TMV0505S")
      (footprint "eagle-import:TMADCDC")
      (libsource (lib "eagle-import") (part "TMV0505"))
    )
    (comp (ref "U3")
      (value "ISO7221XD(SOIC8)")
      (footprint "eagle-import:SO-8_ISOLATE")
      (libsource (lib "eagle-import") (part "ISO7221XD"))
    )
    (comp (ref "U4")
      (value "FT232RL/SSOP28")
      (footprint "eagle-import:SSOP28")
      (libsource (lib "eagle-import") (part "FT232RLSSOP28"))
    )
    (comp (ref "U5")
      (value "INA114BU/1K")
      (footprint "eagle-import:SO16")
      (libsource (lib "eagle-import") (part "INA114BU/1K"))
    )
    (comp (ref "U6")
      (value "INA114BU/1K")
      (footprint "eagle-import:SO16")
      (libsource (lib "eagle-import") (part "INA114BU/1K"))
    )
    (comp (ref "U7")
      (value "NA(USBLC6-2P6)")
      (footprint "eagle-import:USBLC6-2P6")
      (libsource (lib "eagle-import") (part "USBLC6-2"))
    )
    (comp (ref "USB")
      (value "USB_B")
      (footprint "eagle-import:USB_NEAR_BLACK")
      (libsource (lib "eagle-import") (part "USB_SHIELD"))
    )
    (comp (ref "VREF")
      (value "TESTPAD3")
      (footprint "eagle-import:TEST_PAD40_70_SQUARE")
      (libsource (lib "eagle-import") (part "TESTPAD3"))
    )
    (comp (ref "V_CAL")
      (value "TESTPAD3")
      (footprint "eagle-import:TEST_PAD40_70_SQUARE")
      (libsource (lib "eagle-import") (part "TESTPAD3"))
    )
    (comp (ref "Z1")
      (value "BZV55C6V2")
      (footprint "eagle-import:MINI-MELF")
      (libsource (lib "eagle-import") (part "ZDIOD-SMD"))
    )
  )
  (nets
    (net (code "1") (name "+5VA") (class "Default")
      (node (ref "C27") (pin "1") (pinfunction "1_1") (pintype "passive"))
      (node (ref "C28") (pin "1") (pinfunction "1_1") (pintype "passive"))
      (node (ref "C29") (pin "+") (pinfunction "+_+") (pintype "passive"))
      (node (ref "C30") (pin "2") (pinfunction "2_2") (pintype "passive"))
      (node (ref "C33") (pin "1") (pinfunction "1_1") (pintype "passive"))
      (node (ref "C34") (pin "1") (pinfunction "1_1") (pintype "passive"))
      (node (ref "C35") (pin "+") (pinfunction "+_+") (pintype "passive"))
      (node (ref "C45") (pin "1") (pinfunction "1_1") (pintype "passive"))
      (node (ref "C46") (pin "1") (pinfunction "1_1") (pintype "passive"))
      (node (ref "C48") (pin "1") (pinfunction "1_1") (pintype "passive"))
      (node (ref "C49") (pin "1") (pinfunction "1_1") (pintype "passive"))
      (node (ref "C63") (pin "1") (pinfunction "1_1") (pintype "passive"))
      (node (ref "C64") (pin "1") (pinfunction "1_1") (pintype "passive"))
      (node (ref "C66") (pin "1") (pinfunction "1_1") (pintype "passive"))
      (node (ref "C67") (pin "1") (pinfunction "1_1") (pintype "passive"))
      (node (ref "C69") (pin "1") (pinfunction "1_1") (pintype "passive"))
      (node (ref "C70") (pin "1") (pinfunction "1_1") (pintype "passive"))
      (node (ref "D1") (pin "2") (pinfunction "K_2") (pintype "passive"))
      (node (ref "D2") (pin "2") (pinfunction "K_2") (pintype "passive"))
      (node (ref "D3") (pin "2") (pinfunction "K_2") (pintype "passive"))
      (node (ref "D4") (pin "2") (pinfunction "K_2") (pintype "passive"))
      (node (ref "D5") (pin "2") (pinfunction "K_2") (pintype "passive"))
      (node (ref "IC1") (pin "8") (pinfunction "V+_8") (pintype "power_in"))
      (node (ref "IC2") (pin "8") (pinfunction "V+_8") (pintype "power_in"))
      (node (ref "IC3") (pin "8") (pinfunction "V+_8") (pintype "power_in"))
      (node (ref "IC4") (pin "8") (pinfunction "V+_8") (pintype "power_in"))
      (node (ref "L3") (pin "2") (pinfunction "2_2") (pintype "passive"))
      (node (ref "R2") (pin "2") (pinfunction "2_2") (pintype "passive"))
      (node (ref "R3") (pin "2") (pinfunction "2_2") (pintype "passive"))
      (node (ref "R57") (pin "2") (pinfunction "2_2") (pintype "passive"))
      (node (ref "R58") (pin "2") (pinfunction "2_2") (pintype "passive"))
      (node (ref "R59") (pin "2") (pinfunction "2_2") (pintype "passive"))
      (node (ref "R60") (pin "2") (pinfunction "2_2") (pintype "passive"))
      (node (ref "R61") (pin "2") (pinfunction "2_2") (pintype "passive"))
      (node (ref "U5") (pin "13") (pinfunction "V+_13") (pintype "power_in"))
      (node (ref "U6") (pin "13") (pinfunction "V+_13") (pintype "power_in"))
      (node (ref "Z1") (pin "1") (pinfunction "C_1") (pintype "passive"))
    )
    (net (code "2") (name "+5VD") (class "Default")
      (node (ref "C13") (pin "1") (pinfunction "1_1") (pintype "passive"))
      (node (ref "C24") (pin "1") (pinfunction "1_1") (pintype "passive"))
      (node (ref "C25") (pin "1") (pinfunction "1_1") (pintype "passive"))
      (node (ref "C26") (pin "+") (pinfunction "+_+") (pintype "passive"))
      (node (ref "C7") (pin "1") (pinfunction "1_1") (pintype "passive"))
      (node (ref "C72") (pin "1") (pinfunction "1_1") (pintype "passive"))
      (node (ref "C8") (pin "1") (pinfunction "1_1") (pintype "passive"))
      (node (ref "ICSP") (pin "2") (pinfunction "2_2") (pintype "passive"))
      (node (ref "L2") (pin "2") (pinfunction "2_2") (pintype "passive"))
      (node (ref "L3") (pin "1") (pinfunction "1_1") (pintype "passive"))
      (node (ref "R1") (pin "1") (pinfunction "1_1") (pintype "passive"))
      (node (ref "U1") (pin "17") (pinfunction "VCC1_17") (pintype "bidirectional"))
      (node (ref "U1") (pin "38") (pinfunction "VCC2_38") (pintype "bidirectional"))
      (node (ref "U1") (pin "5") (pinfunction "VCC_5") (pintype "power_in"))
      (node (ref "U3") (pin "8") (pinfunction "VCC2_8") (pintype "power_in"))
    )
    (net (code "3") (name "/+5V_USB") (class "Default")
      (node (ref "C14") (pin "1") (pinfunction "1_1") (pintype "passive"))
      (node (ref "C15") (pin "+") (pinfunction "+_+") (pintype "passive"))
      (node (ref "C16") (pin "1") (pinfunction "1_1") (pintype "passive"))
      (node (ref "C17") (pin "1") (pinfunction "1_1") (pintype "passive"))
      (node (ref "FET") (pin "3") (pinfunction "D_3") (pintype "passive"))
      (node (ref "U2") (pin "1") (pinfunction "VIN+_1") (pintype "power_in"))
      (node (ref "U3") (pin "1") (pinfunction "VCC1_1") (pintype "power_in"))
    )
    (net (code "4") (name "/2V_REF") (class "Default")
      (node (ref "C36") (pin "1") (pinfunction "1_1") (pintype "passive"))
      (node (ref "IC4") (pin "3") (pinfunction "+IN_3") (pintype "input"))
      (node (ref "R6") (pin "1") (pinfunction "1_1") (pintype "passive"))
      (node (ref "R7") (pin "2") (pinfunction "2_2") (pintype "passive"))
    )
    (net (code "5") (name "/4V_REF_ADC") (class "Default")
      (node (ref "C5") (pin "1") (pinfunction "1_1") (pintype "passive"))
      (node (ref "C6") (pin "+") (pinfunction "+_+") (pintype "passive"))
      (node (ref "R3") (pin "1") (pinfunction "1_1") (pintype "passive"))
      (node (ref "R4") (pin "2") (pinfunction "2_2") (pintype "passive"))
      (node (ref "R6") (pin "2") (pinfunction "2_2") (pintype "passive"))
      (node (ref "SR1") (pin "1") (pinfunction "C_1") (pintype "input"))
      (node (ref "U1") (pin "29") (pinfunction "AREF_29") (pintype "power_in"))
    )
    (net (code "6") (name "/ADC0") (class "Default")
      (node (ref "C9") (pin "1") (pinfunction "1_1") (pintype "passive"))
      (node (ref "R10") (pin "1") (pinfunction "1_1") (pintype "passive"))
      (node (ref "U1") (pin "37") (pinfunction "(ADC0)PA0_37") (pintype "bidirectional"))
    )
    (net (code "7") (name "/ADC1") (class "Default")
      (node (ref "C10") (pin "1") (pinfunction "1_1") (pintype "passive"))
      (node (ref "R9") (pin "1") (pinfunction "1_1") (pintype "passive"))
      (node (ref "U1") (pin "36") (pinfunction "(ADC1)PA1_36") (pintype "bidirectional"))
    )
    (net (code "8") (name "/CH1_IN+") (class "Default")
      (node (ref "CH1_IN+") (pin "2") (pinfunction "3_2") (pintype "bidirectional"))
      (node (ref "PGS2") (pin "1") (pinfunction "1_1") (pintype "input"))
      (node (ref "R22") (pin "1") (pinfunction "1_1") (pintype "passive"))
    )
    (net (code "9") (name "/CH1_IN-") (class "Default")
      (node (ref "CH1_IN-") (pin "2") (pinfunction "3_2") (pintype "bidirectional"))
      (node (ref "PGS1") (pin "2") (pinfunction "2_2") (pintype "input"))
      (node (ref "R21") (pin "1") (pinfunction "1_1") (pintype "passive"))
    )
    (net (code "10") (name "/CH2_IN+") (class "Default")
      (node (ref "CH2_IN+") (pin "2") (pinfunction "3_2") (pintype "bidirectional"))
      (node (ref "PGS4") (pin "1") (pinfunction "1_1") (pintype "input"))
      (node (ref "R28") (pin "1") (pinfunction "1_1") (pintype "passive"))
    )
    (net (code "11") (name "/CH2_IN-") (class "Default")
      (node (ref "CH2_IN-") (pin "2") (pinfunction "3_2") (pintype "bidirectional"))
      (node (ref "PGS3") (pin "2") (pinfunction "2_2") (pintype "input"))
      (node (ref "R27") (pin "1") (pinfunction "1_1") (pintype "passive"))
    )
    (net (code "12") (name "/DRL") (class "Default")
      (node (ref "DRL") (pin "2") (pinfunction "3_2") (pintype "bidirectional"))
      (node (ref "PGS5") (pin "2") (pinfunction "2_2") (pintype "input"))
      (node (ref "R56") (pin "1") (pinfunction "1_1") (pintype "passive"))
    )
    (net (code "13") (name "/MISO") (class "Default")
      (node (ref "ICSP") (pin "9") (pinfunction "9_9") (pintype "passive"))
      (node (ref "U1") (pin "2") (pinfunction "(MISO)PB6_2") (pintype "bidirectional"))
    )
    (net (code "14") (name "/MOSI") (class "Default")
      (node (ref "ICSP") (pin "1") (pinfunction "1_1") (pintype "passive"))
      (node (ref "U1") (pin "1") (pinfunction "(MOSI)PB5_1") (pintype "bidirectional"))
    )
    (net (code "15") (name "/PD5") (class "Default")
      (node (ref "R20") (pin "2") (pinfunction "2_2") (pintype "passive"))
      (node (ref "U1") (pin "14") (pinfunction "(OC1A)PD5_14") (pintype "bidirectional"))
    )
    (net (code "16") (name "/PWREN") (class "Default")
      (node (ref "R11") (pin "1") (pinfunction "1_1") (pintype "passive"))
      (node (ref "U4") (pin "14") (pinfunction "CBUS3_14") (pintype "bidirectional"))
    )
    (net (code "17") (name "/RST") (class "Default")
      (node (ref "C1") (pin "1") (pinfunction "1_1") (pintype "passive"))
      (node (ref "ICSP") (pin "5") (pinfunction "5_5") (pintype "passive"))
      (node (ref "R1") (pin "2") (pinfunction "2_2") (pintype "passive"))
      (node (ref "RST") (pin "P$1") (pinfunction "PP_P$1") (pintype "passive"))
      (node (ref "U1") (pin "4") (pinfunction "RESET_4") (pintype "input"))
    )
    (net (code "18") (name "/SCK") (class "Default")
      (node (ref "ICSP") (pin "7") (pinfunction "7_7") (pintype "passive"))
      (node (ref "U1") (pin "3") (pinfunction "(SCK)PB7_3") (pintype "bidirectional"))
    )
    (net (code "19") (name "GND") (class "Default")
      (node (ref "C14") (pin "2") (pinfunction "2_2") (pintype "passive"))
      (node (ref "C15") (pin "-") (pinfunction "-_-") (pintype "passive"))
      (node (ref "C16") (pin "2") (pinfunction "2_2") (pintype "passive"))
      (node (ref "C18") (pin "2") (pinfunction "2_2") (pintype "passive"))
      (node (ref "C19") (pin "-") (pinfunction "-_-") (pintype "passive"))
      (node (ref "C20") (pin "2") (pinfunction "2_2") (pintype "passive"))
      (node (ref "C21") (pin "2") (pinfunction "2_2") (pintype "passive"))
      (node (ref "C22") (pin "2") (pinfunction "2_2") (pintype "passive"))
      (node (ref "C23") (pin "2") (pinfunction "2_2") (pintype "passive"))
      (node (ref "C73") (pin "2") (pinfunction "2_2") (pintype "passive"))
      (node (ref "R13") (pin "1") (pinfunction "1_1") (pintype "passive"))
      (node (ref "R63") (pin "1") (pinfunction "1_1") (pintype "passive"))
      (node (ref "U2") (pin "2") (pinfunction "VIN-_2") (pintype "power_in"))
      (node (ref "U3") (pin "4") (pinfunction "GND1_4") (pintype "power_in"))
      (node (ref "U4") (pin "18") (pinfunction "GND_18") (pintype "power_in"))
      (node (ref "U4") (pin "21") (pinfunction "GND_21") (pintype "power_in"))
      (node (ref "U4") (pin "25") (pinfunction "AGND_25") (pintype "power_in"))
      (node (ref "U4") (pin "26") (pinfunction "TEST_26") (pintype "bidirectional"))
      (node (ref "U4") (pin "7") (pinfunction "GND_7") (pintype "power_in"))
      (node (ref "U7") (pin "2") (pinfunction "2_2") (pintype "power_in"))
      (node (ref "USB") (pin "4") (pinfunction "4_4") (pintype "passive"))
    )
    (net (code "20") (name "GNDA") (class "Default")
      (node (ref "AGND") (pin "P$1") (pinfunction "PP_P$1") (pintype "passive"))
      (node (ref "C10") (pin "2") (pinfunction "2_2") (pintype "passive"))
      (node (ref "C27") (pin "2") (pinfunction "2_2") (pintype "passive"))
      (node (ref "C28") (pin "2") (pinfunction "2_2") (pintype "passive"))
      (node (ref "C29") (pin "-") (pinfunction "-_-") (pintype "passive"))
      (node (ref "C31") (pin "2") (pinfunction "2_2") (pintype "passive"))
      (node (ref "C32") (pin "-") (pinfunction "-_-") (pintype "passive"))
      (node (ref "C33") (pin "2") (pinfunction "2_2") (pintype "passive"))
      (node (ref "C34") (pin "2") (pinfunction "2_2") (pintype "passive"))
      (node (ref "C35") (pin "-") (pinfunction "-_-") (pintype "passive"))
      (node (ref "C36") (pin "2") (pinfunction "2_2") (pintype "passive"))
      (node (ref "C39") (pin "1") (pinfunction "1_1") (pintype "passive"))
      (node (ref "C4") (pin "2") (pinfunction "2_2") (pintype "passive"))
      (node (ref "C40") (pin "2") (pinfunction "2_2") (pintype "passive"))
      (node (ref "C41") (pin "1") (pinfunction "1_1") (pintype "passive"))
      (node (ref "C42") (pin "2") (pinfunction "2_2") (pintype "passive"))
      (node (ref "C45") (pin "2") (pinfunction "2_2") (pintype "passive"))
      (node (ref "C47") (pin "1") (pinfunction "1_1") (pintype "passive"))
      (node (ref "C48") (pin "2") (pinfunction "2_2") (pintype "passive"))
      (node (ref "C5") (pin "2") (pinfunction "2_2") (pintype "passive"))
      (node (ref "C50") (pin "1") (pinfunction "1_1") (pintype "passive"))
      (node (ref "C6") (pin "-") (pinfunction "-_-") (pintype "passive"))
      (node (ref "C63") (pin "2") (pinfunction "2_2") (pintype "passive"))
      (node (ref "C65") (pin "1") (pinfunction "1_1") (pintype "passive"))
      (node (ref "C66") (pin "2") (pinfunction "2_2") (pintype "passive"))
      (node (ref "C68") (pin "1") (pinfunction "1_1") (pintype "passive"))
      (node (ref "C70") (pin "2") (pinfunction "2_2") (pintype "passive"))
      (node (ref "C71") (pin "1") (pinfunction "1_1") (pintype "passive"))
      (node (ref "C9") (pin "2") (pinfunction "2_2") (pintype "passive"))
      (node (ref "CH1_IN+") (pin "1") (pinfunction "2_1") (pintype "input"))
      (node (ref "CH1_IN-") (pin "1") (pinfunction "2_1") (pintype "input"))
      (node (ref "CH2_IN+") (pin "1") (pinfunction "2_1") (pintype "input"))
      (node (ref "CH2_IN-") (pin "1") (pinfunction "2_1") (pintype "input"))
      (node (ref "D1") (pin "1") (pinfunction "A_1") (pintype "passive"))
      (node (ref "D2") (pin "1") (pinfunction "A_1") (pintype "passive"))
      (node (ref "D3") (pin "1") (pinfunction "A_1") (pintype "passive"))
      (node (ref "D4") (pin "1") (pinfunction "A_1") (pintype "passive"))
      (node (ref "D5") (pin "1") (pinfunction "A_1") (pintype "passive"))
      (node (ref "DRL") (pin "1") (pinfunction "2_1") (pintype "input"))
      (node (ref "IC1") (pin "4") (pinfunction "V-_4") (pintype "power_in"))
      (node (ref "IC2") (pin "4") (pinfunction "V-_4") (pintype "power_in"))
      (node (ref "IC3") (pin "4") (pinfunction "V-_4") (pintype "power_in"))
      (node (ref "IC4") (pin "4") (pinfunction "V-_4") (pintype "power_in"))
      (node (ref "PGS1") (pin "1") (pinfunction "1_1") (pintype "input"))
      (node (ref "PGS2") (pin "2") (pinfunction "2_2") (pintype "input"))
      (node (ref "PGS3") (pin "1") (pinfunction "1_1") (pintype "input"))
      (node (ref "PGS4") (pin "2") (pinfunction "2_2") (pintype "input"))
      (node (ref "PGS5") (pin "1") (pinfunction "1_1") (pintype "input"))
      (node (ref "R5") (pin "1") (pinfunction "1_1") (pintype "passive"))
      (node (ref "R52") (pin "1") (pinfunction "1.1_1") (pintype "passive"))
      (node (ref "R7") (pin "1") (pinfunction "1_1") (pintype "passive"))
      (node (ref "SR1") (pin "3") (pinfunction "A_3") (pintype "input"))
      (node (ref "TR3") (pin "3") (pinfunction "3_3") (pintype "passive"))
      (node (ref "U1") (pin "28") (pinfunction "AGND_28") (pintype "power_in"))
      (node (ref "U5") (pin "7") (pinfunction "V-_7") (pintype "power_in"))
      (node (ref "U6") (pin "7") (pinfunction "V-_7") (pintype "power_in"))
      (node (ref "Z1") (pin "2") (pinfunction "A_2") (pintype "passive"))
    )
    (net (code "21") (name "Net-(C55-Pad2)") (class "Default")
      (node (ref "C55") (pin "2") (pinfunction "2_2") (pintype "passive"))
      (node (ref "R42") (pin "1") (pinfunction "1_1") (pintype "passive"))
      (node (ref "R44") (pin "1") (pinfunction "1_1") (pintype "passive"))
    )
    (net (code "22") (name "Net-(C56-Pad2)") (class "Default")
      (node (ref "C56") (pin "2") (pinfunction "2_2") (pintype "passive"))
      (node (ref "R43") (pin "1") (pinfunction "1_1") (pintype "passive"))
      (node (ref "R45") (pin "1") (pinfunction "1_1") (pintype "passive"))
    )
    (net (code "23") (name "Net-(C57-Pad1)") (class "Default")
      (node (ref "C57") (pin "1") (pinfunction "1_1") (pintype "passive"))
      (node (ref "R44") (pin "2") (pinfunction "2_2") (pintype "passive"))
      (node (ref "R46") (pin "1") (pinfunction "1_1") (pintype "passive"))
    )
    (net (code "24") (name "Net-(C58-Pad1)") (class "Default")
      (node (ref "C58") (pin "1") (pinfunction "1_1") (pintype "passive"))
      (node (ref "R45") (pin "2") (pinfunction "2_2") (pintype "passive"))
      (node (ref "R47") (pin "1") (pinfunction "1_1") (pintype "passive"))
    )
    (net (code "25") (name "Net-(C73-Pad1)") (class "Default")
      (node (ref "C73") (pin "1") (pinfunction "1_1") (pintype "passive"))
      (node (ref "L1") (pin "1") (pinfunction "1_1") (pintype "passive"))
      (node (ref "U7") (pin "5") (pinfunction "5_5") (pintype "power_in"))
      (node (ref "USB") (pin "1") (pinfunction "1_1") (pintype "passive"))
    )
    (net (code "26") (name "Net-(CH1_IN+-1)") (class "Default")
      (node (ref "CH1_IN+") (pin "5") (pinfunction "1_5") (pintype "bidirectional"))
      (node (ref "R58") (pin "1") (pinfunction "1_1") (pintype "passive"))
    )
    (net (code "27") (name "Net-(CH1_IN--1)") (class "Default")
      (node (ref "CH1_IN-") (pin "5") (pinfunction "1_5") (pintype "bidirectional"))
      (node (ref "R57") (pin "1") (pinfunction "1_1") (pintype "passive"))
    )
    (net (code "28") (name "Net-(CH2_IN+-1)") (class "Default")
      (node (ref "CH2_IN+") (pin "5") (pinfunction "1_5") (pintype "bidirectional"))
      (node (ref "R60") (pin "1") (pinfunction "1_1") (pintype "passive"))
    )
    (net (code "29") (name "Net-(CH2_IN--1)") (class "Default")
      (node (ref "CH2_IN-") (pin "5") (pinfunction "1_5") (pintype "bidirectional"))
      (node (ref "R59") (pin "1") (pinfunction "1_1") (pintype "passive"))
    )
    (net (code "30") (name "Net-(COM-PP)") (class "Default")
      (node (ref "C43") (pin "1") (pinfunction "1_1") (pintype "passive"))
      (node (ref "COM") (pin "P$1") (pinfunction "PP_P$1") (pintype "passive"))
      (node (ref "IC4") (pin "6") (pinfunction "-IN_6") (pintype "input"))
      (node (ref "R33") (pin "1") (pinfunction "1_1") (pintype "passive"))
      (node (ref "R34") (pin "1") (pinfunction "1_1") (pintype "passive"))
    )
    (net (code "31") (name "Net-(D1-AK)") (class "Default")
      (node (ref "C37") (pin "2") (pinfunction "2_2") (pintype "passive"))
      (node (ref "C39") (pin "2") (pinfunction "2_2") (pintype "passive"))
      (node (ref "D1") (pin "3") (pinfunction "AK_3") (pintype "passive"))
      (node (ref "R21") (pin "2") (pinfunction "2_2") (pintype "passive"))
      (node (ref "R23") (pin "2") (pinfunction "2_2") (pintype "passive"))
      (node (ref "R8") (pin "2") (pinfunction "2_2") (pintype "passive"))
    )
    (net (code "32") (name "Net-(D2-AK)") (class "Default")
      (node (ref "C37") (pin "1") (pinfunction "1_1") (pintype "passive"))
      (node (ref "C40") (pin "1") (pinfunction "1_1") (pintype "passive"))
      (node (ref "D2") (pin "3") (pinfunction "AK_3") (pintype "passive"))
      (node (ref "R22") (pin "2") (pinfunction "2_2") (pintype "passive"))
      (node (ref "R26") (pin "2") (pinfunction "2_2") (pintype "passive"))
      (node (ref "R53") (pin "2") (pinfunction "2_2") (pintype "passive"))
    )
    (net (code "33") (name "Net-(D3-AK)") (class "Default")
      (node (ref "C38") (pin "2") (pinfunction "2_2") (pintype "passive"))
      (node (ref "C41") (pin "2") (pinfunction "2_2") (pintype "passive"))
      (node (ref "D3") (pin "3") (pinfunction "AK_3") (pintype "passive"))
      (node (ref "R27") (pin "2") (pinfunction "2_2") (pintype "passive"))
      (node (ref "R29") (pin "2") (pinfunction "2_2") (pintype "passive"))
      (node (ref "R54") (pin "2") (pinfunction "2_2") (pintype "passive"))
    )
    (net (code "34") (name "Net-(D4-AK)") (class "Default")
      (node (ref "C38") (pin "1") (pinfunction "1_1") (pintype "passive"))
      (node (ref "C42") (pin "1") (pinfunction "1_1") (pintype "passive"))
      (node (ref "D4") (pin "3") (pinfunction "AK_3") (pintype "passive"))
      (node (ref "R28") (pin "2") (pinfunction "2_2") (pintype "passive"))
      (node (ref "R32") (pin "2") (pinfunction "2_2") (pintype "passive"))
      (node (ref "R55") (pin "2") (pinfunction "2_2") (pintype "passive"))
    )
    (net (code "35") (name "Net-(D5-AK)") (class "Default")
      (node (ref "C43") (pin "2") (pinfunction "2_2") (pintype "passive"))
      (node (ref "C44") (pin "2") (pinfunction "2_2") (pintype "passive"))
      (node (ref "D5") (pin "3") (pinfunction "AK_3") (pintype "passive"))
      (node (ref "R35") (pin "1") (pinfunction "1_1") (pintype "passive"))
      (node (ref "R56") (pin "2") (pinfunction "2_2") (pintype "passive"))
    )
    (net (code "36") (name "Net-(DRL-1)") (class "Default")
      (node (ref "DRL") (pin "5") (pinfunction "1_5") (pintype "bidirectional"))
      (node (ref "R61") (pin "1") (pinfunction "1_1") (pintype "passive"))
    )
    (net (code "37") (name "Net-(FET-G)") (class "Default")
      (node (ref "C17") (pin "2") (pinfunction "2_2") (pintype "passive"))
      (node (ref "FET") (pin "1") (pinfunction "G_1") (pintype "passive"))
      (node (ref "R11") (pin "2") (pinfunction "2_2") (pintype "passive"))
    )
    (net (code "38") (name "Net-(FET-S)") (class "Default")
      (node (ref "C18") (pin "1") (pinfunction "1_1") (pintype "passive"))
      (node (ref "C19") (pin "+") (pinfunction "+_+") (pintype "passive"))
      (node (ref "FET") (pin "2") (pinfunction "S_2") (pintype "passive"))
      (node (ref "L1") (pin "2") (pinfunction "2_2") (pintype "passive"))
      (node (ref "R12") (pin "2") (pinfunction "2_2") (pintype "passive"))
      (node (ref "U4") (pin "20") (pinfunction "VCC_20") (pintype "power_in"))
      (node (ref "U4") (pin "4") (pinfunction "VCCIO_4") (pintype "power_in"))
    )
    (net (code "39") (name "Net-(GND_CAL-PP)") (class "Default")
      (node (ref "GND_CAL") (pin "P$1") (pinfunction "PP_P$1") (pintype "passive"))
      (node (ref "R18") (pin "1") (pinfunction "1_1") (pintype "passive"))
    )
    (net (code "40") (name "Net-(IC1A-+IN)") (class "Default")
      (node (ref "C51") (pin "2") (pinfunction "2_2") (pintype "passive"))
      (node (ref "IC1") (pin "3") (pinfunction "+IN_3") (pintype "input"))
      (node (ref "R36") (pin "1") (pinfunction "1_1") (pintype "passive"))
    )
    (net (code "41") (name "Net-(IC1A--IN)") (class "Default")
      (node (ref "C53") (pin "1") (pinfunction "1_1") (pintype "passive"))
      (node (ref "IC1") (pin "2") (pinfunction "-IN_2") (pintype "input"))
      (node (ref "R38") (pin "1") (pinfunction "1_1") (pintype "passive"))
      (node (ref "R40") (pin "1") (pinfunction "1_1") (pintype "passive"))
    )
    (net (code "42") (name "Net-(IC1A-OUT)") (class "Default")
      (node (ref "C53") (pin "2") (pinfunction "2_2") (pintype "passive"))
      (node (ref "C55") (pin "1") (pinfunction "1_1") (pintype "passive"))
      (node (ref "IC1") (pin "1") (pinfunction "OUT_1") (pintype "output"))
      (node (ref "R38") (pin "2") (pinfunction "2_2") (pintype "passive"))
    )
    (net (code "43") (name "Net-(IC1B-+IN)") (class "Default")
      (node (ref "C59") (pin "1") (pinfunction "1_1") (pintype "passive"))
      (node (ref "IC1") (pin "5") (pinfunction "+IN_5") (pintype "input"))
      (node (ref "R46") (pin "2") (pinfunction "2_2") (pintype "passive"))
    )
    (net (code "44") (name "Net-(IC1B--IN)") (class "Default")
      (node (ref "C61") (pin "1") (pinfunction "1_1") (pintype "passive"))
      (node (ref "IC1") (pin "6") (pinfunction "-IN_6") (pintype "input"))
      (node (ref "R48") (pin "1") (pinfunction "1_1") (pintype "passive"))
      (node (ref "R50") (pin "1") (pinfunction "1_1") (pintype "passive"))
    )
    (net (code "45") (name "Net-(IC1B-OUT)") (class "Default")
      (node (ref "C57") (pin "2") (pinfunction "2_2") (pintype "passive"))
      (node (ref "C61") (pin "2") (pinfunction "2_2") (pintype "passive"))
      (node (ref "IC1") (pin "7") (pinfunction "OUT_7") (pintype "output"))
      (node (ref "R10") (pin "2") (pinfunction "2_2") (pintype "passive"))
      (node (ref "R50") (pin "2") (pinfunction "2_2") (pintype "passive"))
    )
    (net (code "46") (name "Net-(IC2A-+IN)") (class "Default")
      (node (ref "C52") (pin "2") (pinfunction "2_2") (pintype "passive"))
      (node (ref "IC2") (pin "3") (pinfunction "+IN_3") (pintype "input"))
      (node (ref "R37") (pin "1") (pinfunction "1_1") (pintype "passive"))
    )
    (net (code "47") (name "Net-(IC2A--IN)") (class "Default")
      (node (ref "C54") (pin "1") (pinfunction "1_1") (pintype "passive"))
      (node (ref "IC2") (pin "2") (pinfunction "-IN_2") (pintype "input"))
      (node (ref "R39") (pin "1") (pinfunction "1_1") (pintype "passive"))
      (node (ref "R41") (pin "1") (pinfunction "1_1") (pintype "passive"))
    )
    (net (code "48") (name "Net-(IC2A-OUT)") (class "Default")
      (node (ref "C54") (pin "2") (pinfunction "2_2") (pintype "passive"))
      (node (ref "C56") (pin "1") (pinfunction "1_1") (pintype "passive"))
      (node (ref "IC2") (pin "1") (pinfunction "OUT_1") (pintype "output"))
      (node (ref "R39") (pin "2") (pinfunction "2_2") (pintype "passive"))
    )
    (net (code "49") (name "Net-(IC2B-+IN)") (class "Default")
      (node (ref "C60") (pin "1") (pinfunction "1_1") (pintype "passive"))
      (node (ref "IC2") (pin "5") (pinfunction "+IN_5") (pintype "input"))
      (node (ref "R47") (pin "2") (pinfunction "2_2") (pintype "passive"))
    )
    (net (code "50") (name "Net-(IC2B--IN)") (class "Default")
      (node (ref "C62") (pin "1") (pinfunction "1_1") (pintype "passive"))
      (node (ref "IC2") (pin "6") (pinfunction "-IN_6") (pintype "input"))
      (node (ref "R49") (pin "1") (pinfunction "1_1") (pintype "passive"))
      (node (ref "R51") (pin "1") (pinfunction "1_1") (pintype "passive"))
    )
    (net (code "51") (name "Net-(IC2B-OUT)") (class "Default")
      (node (ref "C58") (pin "2") (pinfunction "2_2") (pintype "passive"))
      (node (ref "C62") (pin "2") (pinfunction "2_2") (pintype "passive"))
      (node (ref "IC2") (pin "7") (pinfunction "OUT_7") (pintype "output"))
      (node (ref "R51") (pin "2") (pinfunction "2_2") (pintype "passive"))
      (node (ref "R9") (pin "2") (pinfunction "2_2") (pintype "passive"))
    )
    (net (code "52") (name "Net-(IC3A-+IN)") (class "Default")
      (node (ref "IC3") (pin "3") (pinfunction "+IN_3") (pintype "input"))
      (node (ref "R30") (pin "2") (pinfunction "2_2") (pintype "passive"))
      (node (ref "R31") (pin "2") (pinfunction "2_2") (pintype "passive"))
    )
    (net (code "53") (name "Net-(IC3A--IN)") (class "Default")
      (node (ref "IC3") (pin "1") (pinfunction "OUT_1") (pintype "output"))
      (node (ref "IC3") (pin "2") (pinfunction "-IN_2") (pintype "input"))
      (node (ref "R34") (pin "2") (pinfunction "2_2") (pintype "passive"))
    )
    (net (code "54") (name "Net-(IC3B-+IN)") (class "Default")
      (node (ref "IC3") (pin "5") (pinfunction "+IN_5") (pintype "input"))
      (node (ref "R24") (pin "2") (pinfunction "2_2") (pintype "passive"))
      (node (ref "R25") (pin "2") (pinfunction "2_2") (pintype "passive"))
    )
    (net (code "55") (name "Net-(IC3B--IN)") (class "Default")
      (node (ref "IC3") (pin "6") (pinfunction "-IN_6") (pintype "input"))
      (node (ref "IC3") (pin "7") (pinfunction "OUT_7") (pintype "output"))
      (node (ref "R33") (pin "2") (pinfunction "2_2") (pintype "passive"))
    )
    (net (code "56") (name "Net-(IC4B-+IN)") (class "Default")
      (node (ref "IC4") (pin "5") (pinfunction "+IN_5") (pintype "input"))
      (node (ref "TR3") (pin "2") (pinfunction "2_2") (pintype "passive"))
      (node (ref "TR3_DIS") (pin "1") (pinfunction "1_1") (pintype "passive"))
    )
    (net (code "57") (name "Net-(IC4B-OUT)") (class "Default")
      (node (ref "C44") (pin "1") (pinfunction "1_1") (pintype "passive"))
      (node (ref "IC4") (pin "7") (pinfunction "OUT_7") (pintype "output"))
      (node (ref "R35") (pin "2") (pinfunction "2_2") (pintype "passive"))
    )
    (net (code "58") (name "Net-(PWR-C)") (class "Default")
      (node (ref "PWR") (pin "K") (pinfunction "C_K") (pintype "passive"))
      (node (ref "R62") (pin "2") (pinfunction "2_2") (pintype "passive"))
    )
    (net (code "59") (name "Net-(R14-1.1)") (class "Default")
      (node (ref "R14") (pin "1") (pinfunction "1.1_1") (pintype "passive"))
      (node (ref "U7") (pin "1") (pinfunction "1_1") (pintype "bidirectional"))
    )
    (net (code "60") (name "Net-(R14-1.2)") (class "Default")
      (node (ref "C20") (pin "1") (pinfunction "1_1") (pintype "passive"))
      (node (ref "R14") (pin "2") (pinfunction "1.2_2") (pintype "passive"))
      (node (ref "U4") (pin "16") (pinfunction "USBDM_16") (pintype "bidirectional"))
    )
    (net (code "61") (name "Net-(R15-1.1)") (class "Default")
      (node (ref "R15") (pin "1") (pinfunction "1.1_1") (pintype "passive"))
      (node (ref "U7") (pin "3") (pinfunction "3_3") (pintype "bidirectional"))
    )
    (net (code "62") (name "Net-(R15-1.2)") (class "Default")
      (node (ref "C21") (pin "1") (pinfunction "1_1") (pintype "passive"))
      (node (ref "R15") (pin "2") (pinfunction "1.2_2") (pintype "passive"))
      (node (ref "U4") (pin "15") (pinfunction "USBDP_15") (pintype "bidirectional"))
    )
    (net (code "63") (name "Net-(R16-Pad2)") (class "Default")
      (node (ref "R16") (pin "2") (pinfunction "2_2") (pintype "passive"))
      (node (ref "R17") (pin "2") (pinfunction "2_2") (pintype "passive"))
      (node (ref "R19") (pin "1") (pinfunction "1_1") (pintype "passive"))
    )
    (net (code "64") (name "Net-(R19-Pad2)") (class "Default")
      (node (ref "R19") (pin "2") (pinfunction "2_2") (pintype "passive"))
      (node (ref "R20") (pin "1") (pinfunction "1_1") (pintype "passive"))
    )
    (net (code "65") (name "Net-(R24-Pad1)") (class "Default")
      (node (ref "R24") (pin "1") (pinfunction "1_1") (pintype "passive"))
      (node (ref "U5") (pin "2") (pinfunction "RG_2") (pintype "passive"))
    )
    (net (code "66") (name "Net-(R25-Pad1)") (class "Default")
      (node (ref "R25") (pin "1") (pinfunction "1_1") (pintype "passive"))
      (node (ref "U5") (pin "15") (pinfunction "RG_15") (pintype "passive"))
    )
    (net (code "67") (name "Net-(R30-Pad1)") (class "Default")
      (node (ref "R30") (pin "1") (pinfunction "1_1") (pintype "passive"))
      (node (ref "U6") (pin "2") (pinfunction "RG_2") (pintype "passive"))
    )
    (net (code "68") (name "Net-(R31-Pad1)") (class "Default")
      (node (ref "R31") (pin "1") (pinfunction "1_1") (pintype "passive"))
      (node (ref "U6") (pin "15") (pinfunction "RG_15") (pintype "passive"))
    )
    (net (code "69") (name "Net-(R40-Pad2)") (class "Default")
      (node (ref "R40") (pin "2") (pinfunction "2_2") (pintype "passive"))
      (node (ref "TR1") (pin "1") (pinfunction "1_1") (pintype "passive"))
    )
    (net (code "70") (name "Net-(R41-Pad2)") (class "Default")
      (node (ref "R41") (pin "2") (pinfunction "2_2") (pintype "passive"))
      (node (ref "TR2") (pin "1") (pinfunction "1_1") (pintype "passive"))
    )
    (net (code "71") (name "Net-(SR1-R)") (class "Default")
      (node (ref "R4") (pin "1") (pinfunction "1_1") (pintype "passive"))
      (node (ref "R5") (pin "2") (pinfunction "2_2") (pintype "passive"))
      (node (ref "SR1") (pin "2") (pinfunction "R_2") (pintype "input"))
    )
    (net (code "72") (name "Net-(TCK-PP)") (class "Default")
      (node (ref "TCK") (pin "P$1") (pinfunction "PP_P$1") (pintype "passive"))
      (node (ref "U1") (pin "21") (pinfunction "PC2(TCK)_21") (pintype "bidirectional"))
    )
    (net (code "73") (name "Net-(TDI-PP)") (class "Default")
      (node (ref "TDI") (pin "P$1") (pinfunction "PP_P$1") (pintype "passive"))
      (node (ref "U1") (pin "24") (pinfunction "PC5(TDI)_24") (pintype "bidirectional"))
    )
    (net (code "74") (name "Net-(TDO-PP)") (class "Default")
      (node (ref "TDO") (pin "P$1") (pinfunction "PP_P$1") (pintype "passive"))
      (node (ref "U1") (pin "23") (pinfunction "PC4(TDO)_23") (pintype "bidirectional"))
    )
    (net (code "75") (name "Net-(TMS-PP)") (class "Default")
      (node (ref "TMS") (pin "P$1") (pinfunction "PP_P$1") (pintype "passive"))
      (node (ref "U1") (pin "22") (pinfunction "PC3(TMS)_22") (pintype "bidirectional"))
    )
    (net (code "76") (name "Net-(U1-(RXD)PD0)") (class "Default")
      (node (ref "U1") (pin "9") (pinfunction "(RXD)PD0_9") (pintype "bidirectional"))
      (node (ref "U3") (pin "6") (pinfunction "OUTB_6") (pintype "output"))
    )
    (net (code "77") (name "Net-(U1-(TXD)PD1)") (class "Default")
      (node (ref "U1") (pin "10") (pinfunction "(TXD)PD1_10") (pintype "bidirectional"))
      (node (ref "U3") (pin "7") (pinfunction "INA_7") (pintype "input"))
    )
    (net (code "78") (name "Net-(U1-AVCC)") (class "Default")
      (node (ref "C4") (pin "1") (pinfunction "1_1") (pintype "passive"))
      (node (ref "R2") (pin "1") (pinfunction "1_1") (pintype "passive"))
      (node (ref "U1") (pin "27") (pinfunction "AVCC_27") (pintype "power_in"))
    )
    (net (code "79") (name "Net-(U1-XTAL1)") (class "Default")
      (node (ref "C3") (pin "1") (pinfunction "1_1") (pintype "passive"))
      (node (ref "Q1") (pin "2") (pinfunction "2_2") (pintype "passive"))
      (node (ref "U1") (pin "8") (pinfunction "XTAL1_8") (pintype "bidirectional"))
    )
    (net (code "80") (name "Net-(U1-XTAL2)") (class "Default")
      (node (ref "C2") (pin "1") (pinfunction "1_1") (pintype "passive"))
      (node (ref "Q1") (pin "1") (pinfunction "1_1") (pintype "passive"))
      (node (ref "U1") (pin "7") (pinfunction "XTAL2_7") (pintype "bidirectional"))
    )
    (net (code "81") (name "Net-(U3-INB)") (class "Default")
      (node (ref "U3") (pin "3") (pinfunction "INB_3") (pintype "input"))
      (node (ref "U4") (pin "1") (pinfunction "TXD_1") (pintype "output"))
    )
    (net (code "82") (name "Net-(U3-OUTA)") (class "Default")
      (node (ref "U3") (pin "2") (pinfunction "OUTA_2") (pintype "output"))
      (node (ref "U4") (pin "5") (pinfunction "RXD_5") (pintype "input"))
    )
    (net (code "83") (name "Net-(U4-#RESET)") (class "Default")
      (node (ref "R12") (pin "1") (pinfunction "1_1") (pintype "passive"))
      (node (ref "R13") (pin "2") (pinfunction "2_2") (pintype "passive"))
      (node (ref "U4") (pin "19") (pinfunction "#RESET_19") (pintype "input"))
    )
    (net (code "84") (name "Net-(U4-3V3OUT)") (class "Default")
      (node (ref "C23") (pin "1") (pinfunction "1_1") (pintype "passive"))
      (node (ref "U4") (pin "17") (pinfunction "3V3OUT_17") (pintype "output"))
    )
    (net (code "85") (name "Net-(U5-FB)") (class "Default")
      (node (ref "C51") (pin "1") (pinfunction "1_1") (pintype "passive"))
      (node (ref "U5") (pin "11") (pinfunction "VO_11") (pintype "output"))
      (node (ref "U5") (pin "12") (pinfunction "FB_12") (pintype "input"))
    )
    (net (code "86") (name "Net-(U5-V+IN)") (class "Default")
      (node (ref "R26") (pin "1") (pinfunction "1_1") (pintype "passive"))
      (node (ref "U5") (pin "5") (pinfunction "V+IN_5") (pintype "input"))
    )
    (net (code "87") (name "Net-(U5-V-IN)") (class "Default")
      (node (ref "R23") (pin "1") (pinfunction "1_1") (pintype "passive"))
      (node (ref "U5") (pin "4") (pinfunction "V-IN_4") (pintype "input"))
    )
    (net (code "88") (name "Net-(U6-FB)") (class "Default")
      (node (ref "C52") (pin "1") (pinfunction "1_1") (pintype "passive"))
      (node (ref "U6") (pin "11") (pinfunction "VO_11") (pintype "output"))
      (node (ref "U6") (pin "12") (pinfunction "FB_12") (pintype "input"))
    )
    (net (code "89") (name "Net-(U6-V+IN)") (class "Default")
      (node (ref "R32") (pin "1") (pinfunction "1_1") (pintype "passive"))
      (node (ref "U6") (pin "5") (pinfunction "V+IN_5") (pintype "input"))
    )
    (net (code "90") (name "Net-(U6-V-IN)") (class "Default")
      (node (ref "R29") (pin "1") (pinfunction "1_1") (pintype "passive"))
      (node (ref "U6") (pin "4") (pinfunction "V-IN_4") (pintype "input"))
    )
    (net (code "91") (name "Net-(U7-Pad4)") (class "Default")
      (node (ref "U7") (pin "4") (pinfunction "4_4") (pintype "bidirectional"))
      (node (ref "USB") (pin "3") (pinfunction "3_3") (pintype "passive"))
    )
    (net (code "92") (name "Net-(U7-Pad6)") (class "Default")
      (node (ref "U7") (pin "6") (pinfunction "6_6") (pintype "bidirectional"))
      (node (ref "USB") (pin "2") (pinfunction "2_2") (pintype "passive"))
    )
    (net (code "93") (name "Net-(USB-5)") (class "Default")
      (node (ref "C22") (pin "1") (pinfunction "1_1") (pintype "passive"))
      (node (ref "R63") (pin "2") (pinfunction "2_2") (pintype "passive"))
      (node (ref "USB") (pin "P$1") (pinfunction "5_P$1") (pintype "input"))
      (node (ref "USB") (pin "P$2") (pinfunction "6_P$2") (pintype "input"))
    )
    (net (code "94") (name "Net-(V_CAL-PP)") (class "Default")
      (node (ref "R16") (pin "1") (pinfunction "1_1") (pintype "passive"))
      (node (ref "V_CAL") (pin "P$1") (pinfunction "PP_P$1") (pintype "passive"))
    )
    (net (code "95") (name "PE") (class "Default")
      (node (ref "C1") (pin "2") (pinfunction "2_2") (pintype "passive"))
      (node (ref "C11") (pin "-") (pinfunction "-_-") (pintype "passive"))
      (node (ref "C12") (pin "2") (pinfunction "2_2") (pintype "passive"))
      (node (ref "C13") (pin "2") (pinfunction "2_2") (pintype "passive"))
      (node (ref "C2") (pin "2") (pinfunction "2_2") (pintype "passive"))
      (node (ref "C24") (pin "2") (pinfunction "2_2") (pintype "passive"))
      (node (ref "C25") (pin "2") (pinfunction "2_2") (pintype "passive"))
      (node (ref "C26") (pin "-") (pinfunction "-_-") (pintype "passive"))
      (node (ref "C3") (pin "2") (pinfunction "2_2") (pintype "passive"))
      (node (ref "C7") (pin "2") (pinfunction "2_2") (pintype "passive"))
      (node (ref "C72") (pin "2") (pinfunction "2_2") (pintype "passive"))
      (node (ref "C8") (pin "2") (pinfunction "2_2") (pintype "passive"))
      (node (ref "ICSP") (pin "10") (pinfunction "10_10") (pintype "passive"))
      (node (ref "ICSP") (pin "4") (pinfunction "4_4") (pintype "passive"))
      (node (ref "ICSP") (pin "6") (pinfunction "6_6") (pintype "passive"))
      (node (ref "ICSP") (pin "8") (pinfunction "8_8") (pintype "passive"))
      (node (ref "R52") (pin "2") (pinfunction "1.2_2") (pintype "passive"))
      (node (ref "R62") (pin "1") (pinfunction "1_1") (pintype "passive"))
      (node (ref "U1") (pin "18") (pinfunction "GND1_18") (pintype "bidirectional"))
      (node (ref "U1") (pin "39") (pinfunction "GND2_39") (pintype "bidirectional"))
      (node (ref "U1") (pin "6") (pinfunction "GND_6") (pintype "power_in"))
      (node (ref "U2") (pin "5") (pinfunction "VOUT-_5") (pintype "power_in"))
      (node (ref "U3") (pin "5") (pinfunction "GND2_5") (pintype "power_in"))
    )
    (net (code "96") (name "VIN") (class "Default")
      (node (ref "C11") (pin "+") (pinfunction "+_+") (pintype "passive"))
      (node (ref "C12") (pin "1") (pinfunction "1_1") (pintype "passive"))
      (node (ref "L2") (pin "1") (pinfunction "1_1") (pintype "passive"))
      (node (ref "PWR") (pin "A") (pinfunction "A_A") (pintype "passive"))
      (node (ref "U2") (pin "7") (pinfunction "VOUT+_7") (pintype "power_in"))
    )
    (net (code "97") (name "V_REF") (class "Default")
      (node (ref "C30") (pin "1") (pinfunction "1_1") (pintype "passive"))
      (node (ref "C31") (pin "1") (pinfunction "1_1") (pintype "passive"))
      (node (ref "C32") (pin "+") (pinfunction "+_+") (pintype "passive"))
      (node (ref "C46") (pin "2") (pinfunction "2_2") (pintype "passive"))
      (node (ref "C47") (pin "2") (pinfunction "2_2") (pintype "passive"))
      (node (ref "C49") (pin "2") (pinfunction "2_2") (pintype "passive"))
      (node (ref "C50") (pin "2") (pinfunction "2_2") (pintype "passive"))
      (node (ref "C59") (pin "2") (pinfunction "2_2") (pintype "passive"))
      (node (ref "C60") (pin "2") (pinfunction "2_2") (pintype "passive"))
      (node (ref "C64") (pin "2") (pinfunction "2_2") (pintype "passive"))
      (node (ref "C65") (pin "2") (pinfunction "2_2") (pintype "passive"))
      (node (ref "C67") (pin "2") (pinfunction "2_2") (pintype "passive"))
      (node (ref "C68") (pin "2") (pinfunction "2_2") (pintype "passive"))
      (node (ref "C69") (pin "2") (pinfunction "2_2") (pintype "passive"))
      (node (ref "C71") (pin "2") (pinfunction "2_2") (pintype "passive"))
      (node (ref "IC4") (pin "1") (pinfunction "OUT_1") (pintype "output"))
      (node (ref "IC4") (pin "2") (pinfunction "-IN_2") (pintype "input"))
      (node (ref "R17") (pin "1") (pinfunction "1_1") (pintype "passive"))
      (node (ref "R18") (pin "2") (pinfunction "2_2") (pintype "passive"))
      (node (ref "R36") (pin "2") (pinfunction "2_2") (pintype "passive"))
      (node (ref "R37") (pin "2") (pinfunction "2_2") (pintype "passive"))
      (node (ref "R42") (pin "2") (pinfunction "2_2") (pintype "passive"))
      (node (ref "R43") (pin "2") (pinfunction "2_2") (pintype "passive"))
      (node (ref "R48") (pin "2") (pinfunction "2_2") (pintype "passive"))
      (node (ref "R49") (pin "2") (pinfunction "2_2") (pintype "passive"))
      (node (ref "R53") (pin "1") (pinfunction "1_1") (pintype "passive"))
      (node (ref "R54") (pin "1") (pinfunction "1_1") (pintype "passive"))
      (node (ref "R55") (pin "1") (pinfunction "1_1") (pintype "passive"))
      (node (ref "R8") (pin "1") (pinfunction "1_1") (pintype "passive"))
      (node (ref "TR1") (pin "2") (pinfunction "2_2") (pintype "passive"))
      (node (ref "TR1") (pin "3") (pinfunction "3_3") (pintype "passive"))
      (node (ref "TR2") (pin "2") (pinfunction "2_2") (pintype "passive"))
      (node (ref "TR2") (pin "3") (pinfunction "3_3") (pintype "passive"))
      (node (ref "TR3") (pin "1") (pinfunction "1_1") (pintype "passive"))
      (node (ref "TR3_DIS") (pin "2") (pinfunction "2_2") (pintype "passive"))
      (node (ref "U5") (pin "10") (pinfunction "REF_10") (pintype "input"))
      (node (ref "U6") (pin "10") (pinfunction "REF_10") (pintype "input"))
      (node (ref "VREF") (pin "P$1") (pinfunction "PP_P$1") (pintype "passive"))
    )
    (net (code "98") (name "unconnected-(ICSP-Pad3)") (class "Default")
      (node (ref "ICSP") (pin "3") (pinfunction "3_3") (pintype "passive"))
    )
    (net (code "99") (name "unconnected-(U1-(ADC2)PA2-Pad35)") (class "Default")
      (node (ref "U1") (pin "35") (pinfunction "(ADC2)PA2_35") (pintype "bidirectional"))
    )
    (net (code "100") (name "unconnected-(U1-(ADC3)PA3-Pad34)") (class "Default")
      (node (ref "U1") (pin "34") (pinfunction "(ADC3)PA3_34") (pintype "bidirectional"))
    )
    (net (code "101") (name "unconnected-(U1-(ADC4)PA4-Pad33)") (class "Default")
      (node (ref "U1") (pin "33") (pinfunction "(ADC4)PA4_33") (pintype "bidirectional"))
    )
    (net (code "102") (name "unconnected-(U1-(ADC5)PA5-Pad32)") (class "Default")
      (node (ref "U1") (pin "32") (pinfunction "(ADC5)PA5_32") (pintype "bidirectional"))
    )
    (net (code "103") (name "unconnected-(U1-(ADC6)PA6-Pad31)") (class "Default")
      (node (ref "U1") (pin "31") (pinfunction "(ADC6)PA6_31") (pintype "bidirectional"))
    )
    (net (code "104") (name "unconnected-(U1-(ADC7)PA7-Pad30)") (class "Default")
      (node (ref "U1") (pin "30") (pinfunction "(ADC7)PA7_30") (pintype "bidirectional"))
    )
    (net (code "105") (name "unconnected-(U1-(AIN0{slash}INT2)PB2-Pad42)") (class "Default")
      (node (ref "U1") (pin "42") (pinfunction "(AIN0/INT2)PB2_42") (pintype "bidirectional"))
    )
    (net (code "106") (name "unconnected-(U1-(AIN1)PB3-Pad43)") (class "Default")
      (node (ref "U1") (pin "43") (pinfunction "(AIN1)PB3_43") (pintype "bidirectional"))
    )
    (net (code "107") (name "unconnected-(U1-(ICP)PD6-Pad15)") (class "Default")
      (node (ref "U1") (pin "15") (pinfunction "(ICP)PD6_15") (pintype "bidirectional"))
    )
    (net (code "108") (name "unconnected-(U1-(INT0)PD2-Pad11)") (class "Default")
      (node (ref "U1") (pin "11") (pinfunction "(INT0)PD2_11") (pintype "bidirectional"))
    )
    (net (code "109") (name "unconnected-(U1-(INT1)PD3-Pad12)") (class "Default")
      (node (ref "U1") (pin "12") (pinfunction "(INT1)PD3_12") (pintype "bidirectional"))
    )
    (net (code "110") (name "unconnected-(U1-(OC1B)PD4-Pad13)") (class "Default")
      (node (ref "U1") (pin "13") (pinfunction "(OC1B)PD4_13") (pintype "bidirectional"))
    )
    (net (code "111") (name "unconnected-(U1-(OC2)PD7-Pad16)") (class "Default")
      (node (ref "U1") (pin "16") (pinfunction "(OC2)PD7_16") (pintype "bidirectional"))
    )
    (net (code "112") (name "unconnected-(U1-(SS)PB4-Pad44)") (class "Default")
      (node (ref "U1") (pin "44") (pinfunction "(SS)PB4_44") (pintype "bidirectional"))
    )
    (net (code "113") (name "unconnected-(U1-(T0)PB0-Pad40)") (class "Default")
      (node (ref "U1") (pin "40") (pinfunction "(T0)PB0_40") (pintype "bidirectional"))
    )
    (net (code "114") (name "unconnected-(U1-(T1)PB1-Pad41)") (class "Default")
      (node (ref "U1") (pin "41") (pinfunction "(T1)PB1_41") (pintype "bidirectional"))
    )
    (net (code "115") (name "unconnected-(U1-(TOSC1)PC6-Pad25)") (class "Default")
      (node (ref "U1") (pin "25") (pinfunction "(TOSC1)PC6_25") (pintype "bidirectional"))
    )
    (net (code "116") (name "unconnected-(U1-(TOSC2)PC7-Pad26)") (class "Default")
      (node (ref "U1") (pin "26") (pinfunction "(TOSC2)PC7_26") (pintype "bidirectional"))
    )
    (net (code "117") (name "unconnected-(U1-PC0(SCL)-Pad19)") (class "Default")
      (node (ref "U1") (pin "19") (pinfunction "PC0(SCL)_19") (pintype "bidirectional"))
    )
    (net (code "118") (name "unconnected-(U1-PC1(SDA)-Pad20)") (class "Default")
      (node (ref "U1") (pin "20") (pinfunction "PC1(SDA)_20") (pintype "bidirectional"))
    )
    (net (code "119") (name "unconnected-(U4-CBUS0-Pad23)") (class "Default")
      (node (ref "U4") (pin "23") (pinfunction "CBUS0_23") (pintype "bidirectional"))
    )
    (net (code "120") (name "unconnected-(U4-CBUS1-Pad22)") (class "Default")
      (node (ref "U4") (pin "22") (pinfunction "CBUS1_22") (pintype "bidirectional"))
    )
    (net (code "121") (name "unconnected-(U4-CBUS2-Pad13)") (class "Default")
      (node (ref "U4") (pin "13") (pinfunction "CBUS2_13") (pintype "bidirectional"))
    )
    (net (code "122") (name "unconnected-(U4-CBUS4-Pad12)") (class "Default")
      (node (ref "U4") (pin "12") (pinfunction "CBUS4_12") (pintype "bidirectional"))
    )
    (net (code "123") (name "unconnected-(U4-CTS#-Pad11)") (class "Default")
      (node (ref "U4") (pin "11") (pinfunction "CTS#_11") (pintype "input"))
    )
    (net (code "124") (name "unconnected-(U4-DCD#-Pad10)") (class "Default")
      (node (ref "U4") (pin "10") (pinfunction "DCD#_10") (pintype "input"))
    )
    (net (code "125") (name "unconnected-(U4-DSR#-Pad9)") (class "Default")
      (node (ref "U4") (pin "9") (pinfunction "DSR#_9") (pintype "input"))
    )
    (net (code "126") (name "unconnected-(U4-DTR#-Pad2)") (class "Default")
      (node (ref "U4") (pin "2") (pinfunction "DTR#_2") (pintype "output"))
    )
    (net (code "127") (name "unconnected-(U4-NC1-Pad8)") (class "Default")
      (node (ref "U4") (pin "8") (pinfunction "NC1_8") (pintype "no_connect"))
    )
    (net (code "128") (name "unconnected-(U4-NC2-Pad24)") (class "Default")
      (node (ref "U4") (pin "24") (pinfunction "NC2_24") (pintype "no_connect"))
    )
    (net (code "129") (name "unconnected-(U4-OSCI-Pad27)") (class "Default")
      (node (ref "U4") (pin "27") (pinfunction "OSCI_27") (pintype "input"))
    )
    (net (code "130") (name "unconnected-(U4-OSCO-Pad28)") (class "Default")
      (node (ref "U4") (pin "28") (pinfunction "OSCO_28") (pintype "output"))
    )
    (net (code "131") (name "unconnected-(U4-RI#-Pad6)") (class "Default")
      (node (ref "U4") (pin "6") (pinfunction "RI#_6") (pintype "input"))
    )
    (net (code "132") (name "unconnected-(U4-RTS#-Pad3)") (class "Default")
      (node (ref "U4") (pin "3") (pinfunction "RTS#_3") (pintype "output"))
    )
    (net (code "133") (name "unconnected-(U5-NC-Pad1)") (class "Default")
      (node (ref "U5") (pin "1") (pinfunction "NC_1") (pintype "no_connect"))
    )
    (net (code "134") (name "unconnected-(U5-NC-Pad3)") (class "Default")
      (node (ref "U5") (pin "3") (pinfunction "NC_3") (pintype "no_connect"))
    )
    (net (code "135") (name "unconnected-(U5-NC-Pad6)") (class "Default")
      (node (ref "U5") (pin "6") (pinfunction "NC_6") (pintype "no_connect"))
    )
    (net (code "136") (name "unconnected-(U5-NC-Pad8)") (class "Default")
      (node (ref "U5") (pin "8") (pinfunction "NC_8") (pintype "no_connect"))
    )
    (net (code "137") (name "unconnected-(U5-NC-Pad9)") (class "Default")
      (node (ref "U5") (pin "9") (pinfunction "NC_9") (pintype "no_connect"))
    )
    (net (code "138") (name "unconnected-(U5-NC-Pad14)") (class "Default")
      (node (ref "U5") (pin "14") (pinfunction "NC_14") (pintype "no_connect"))
    )
    (net (code "139") (name "unconnected-(U5-NC-Pad16)") (class "Default")
      (node (ref "U5") (pin "16") (pinfunction "NC_16") (pintype "no_connect"))
    )
    (net (code "140") (name "unconnected-(U6-NC-Pad1)") (class "Default")
      (node (ref "U6") (pin "1") (pinfunction "NC_1") (pintype "no_connect"))
    )
    (net (code "141") (name "unconnected-(U6-NC-Pad3)") (class "Default")
      (node (ref "U6") (pin "3") (pinfunction "NC_3") (pintype "no_connect"))
    )
    (net (code "142") (name "unconnected-(U6-NC-Pad6)") (class "Default")
      (node (ref "U6") (pin "6") (pinfunction "NC_6") (pintype "no_connect"))
    )
    (net (code "143") (name "unconnected-(U6-NC-Pad8)") (class "Default")
      (node (ref "U6") (pin "8") (pinfunction "NC_8") (pintype "no_connect"))
    )
    (net (code "144") (name "unconnected-(U6-NC-Pad9)") (class "Default")
      (node (ref "U6") (pin "9") (pinfunction "NC_9") (pintype "no_connect"))
    )
    (net (code "145") (name "unconnected-(U6-NC-Pad14)") (class "Default")
      (node (ref "U6") (pin "14") (pinfunction "NC_14") (pintype "no_connect"))
    )
    (net (code "146") (name "unconnected-(U6-NC-Pad16)") (class "Default")
      (node (ref "U6") (pin "16") (pinfunction "NC_16") (pintype "no_connect"))
    )
  )
)
